# IF_TEST_1.net
KiCad netlist of a schematic drawn in EAGLE
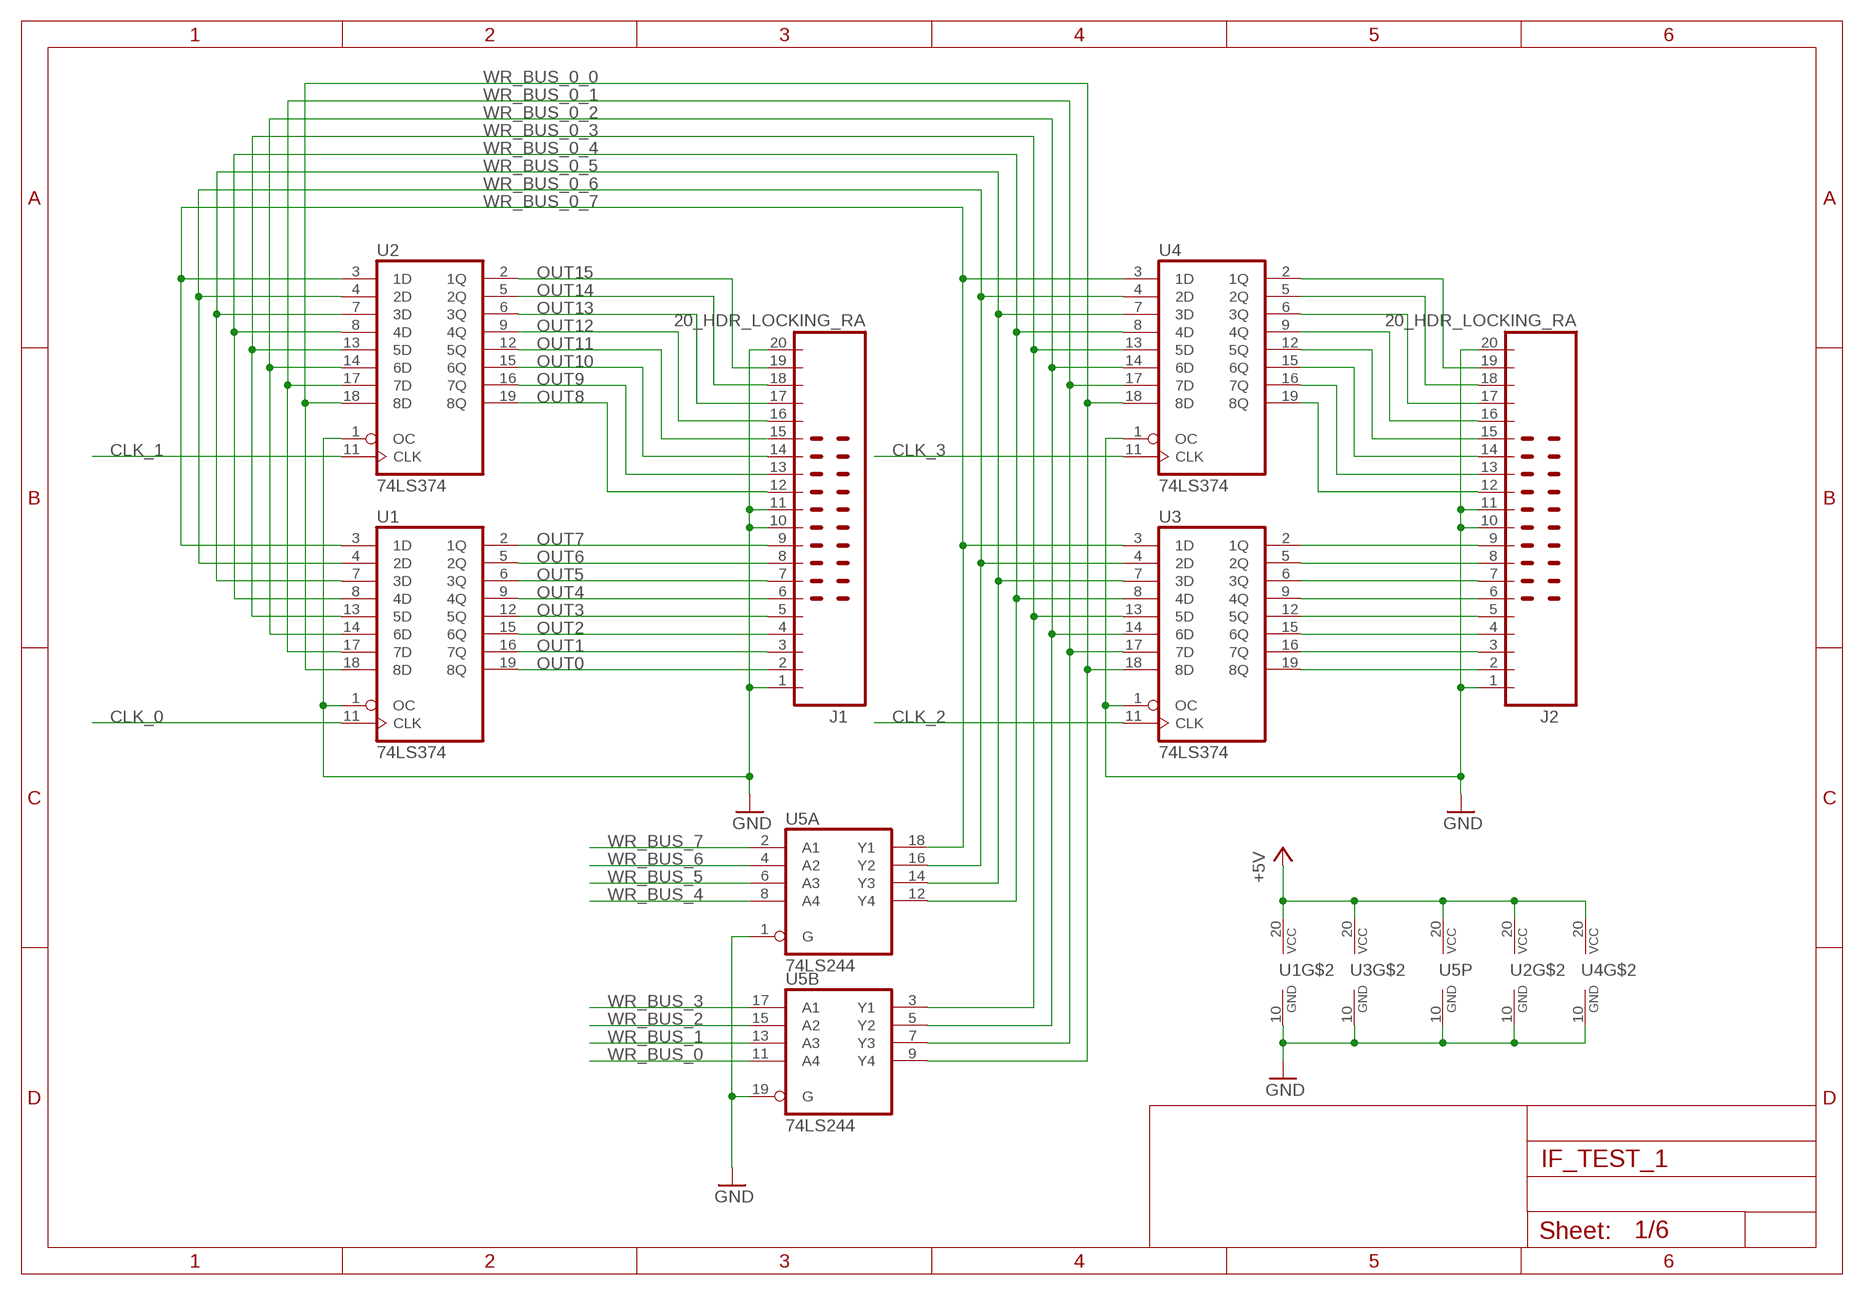
[diagram p0: schematic, sheet 1]
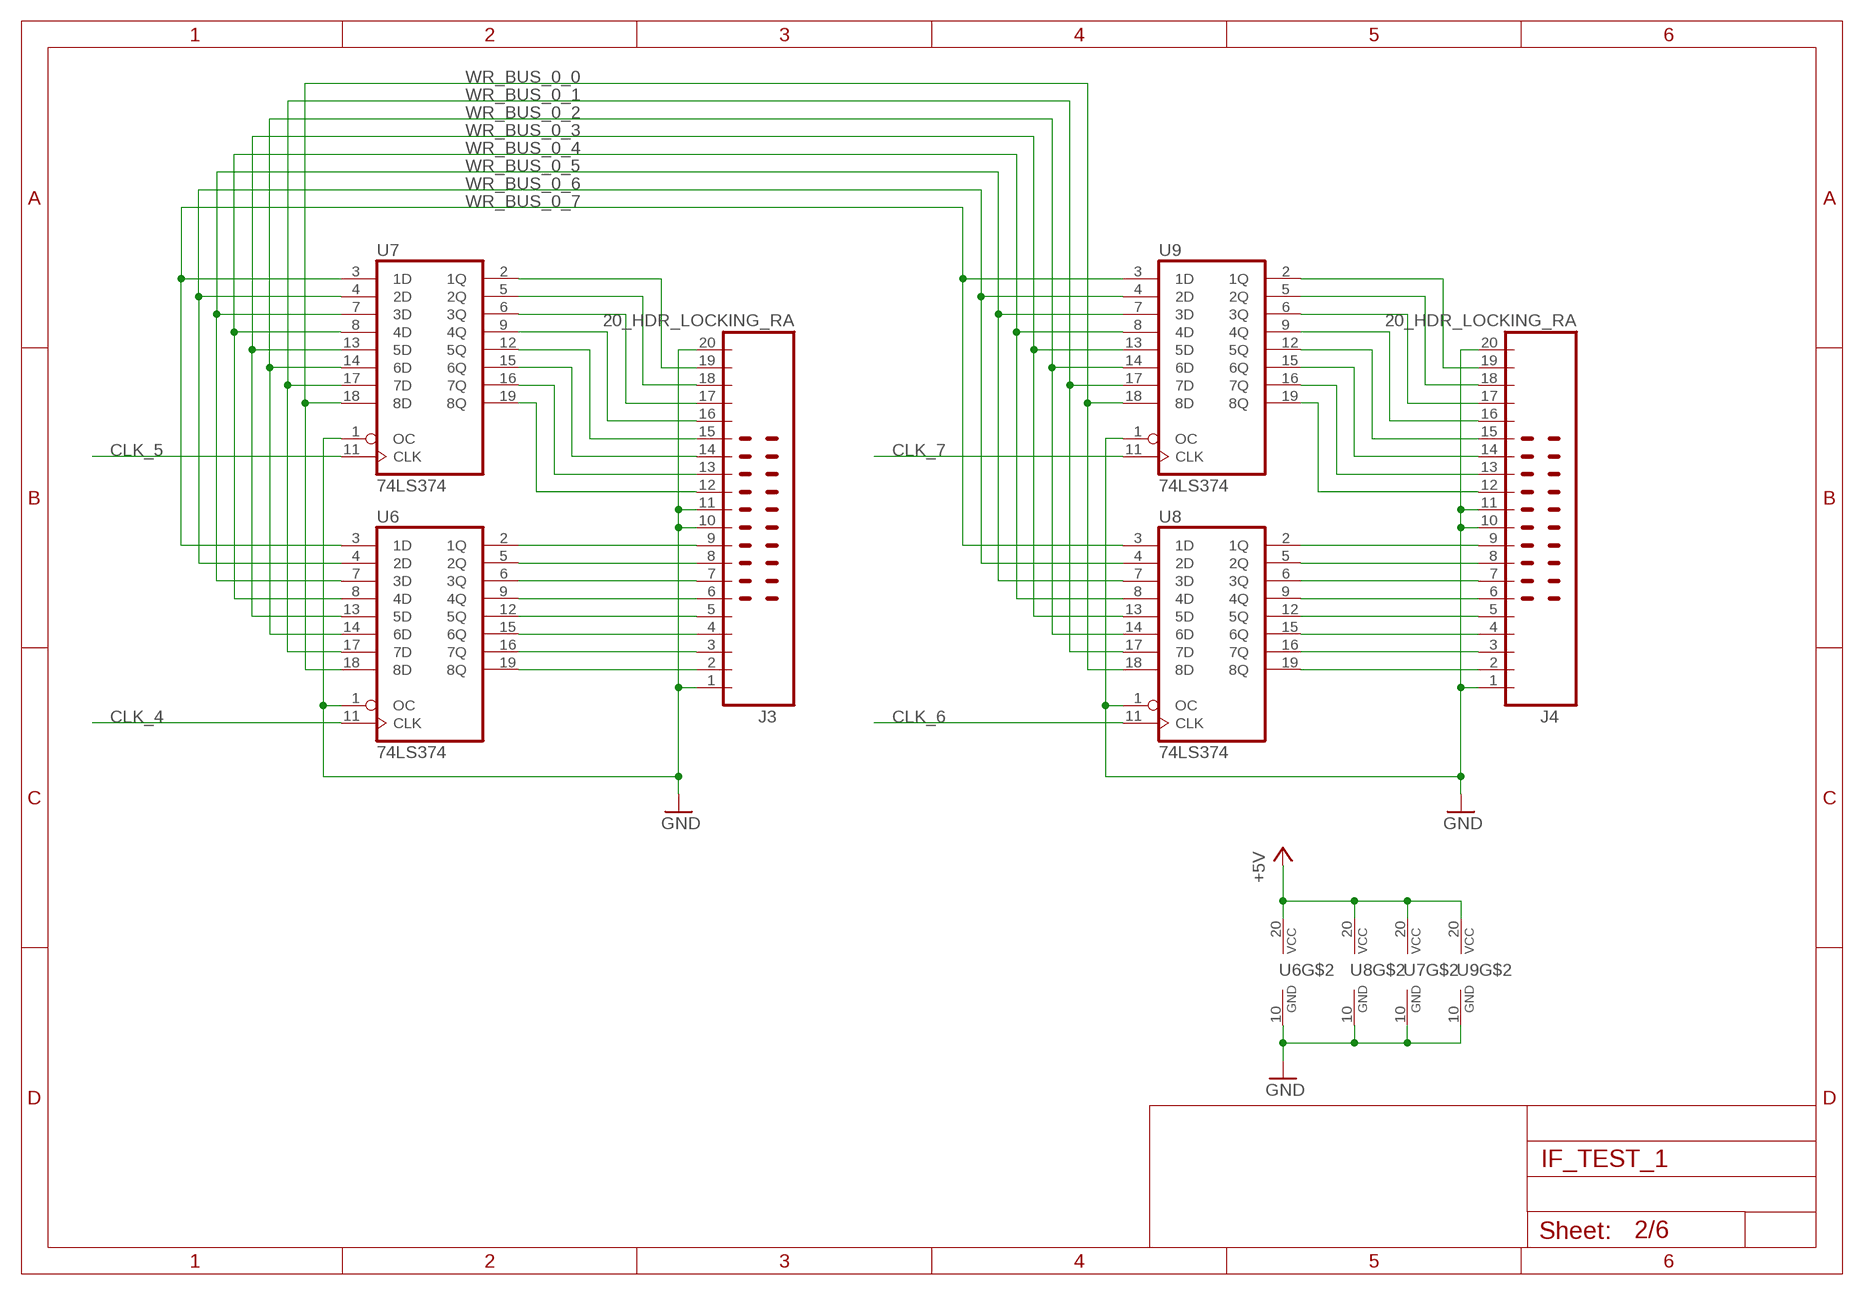
[diagram p1: schematic, sheet 2]
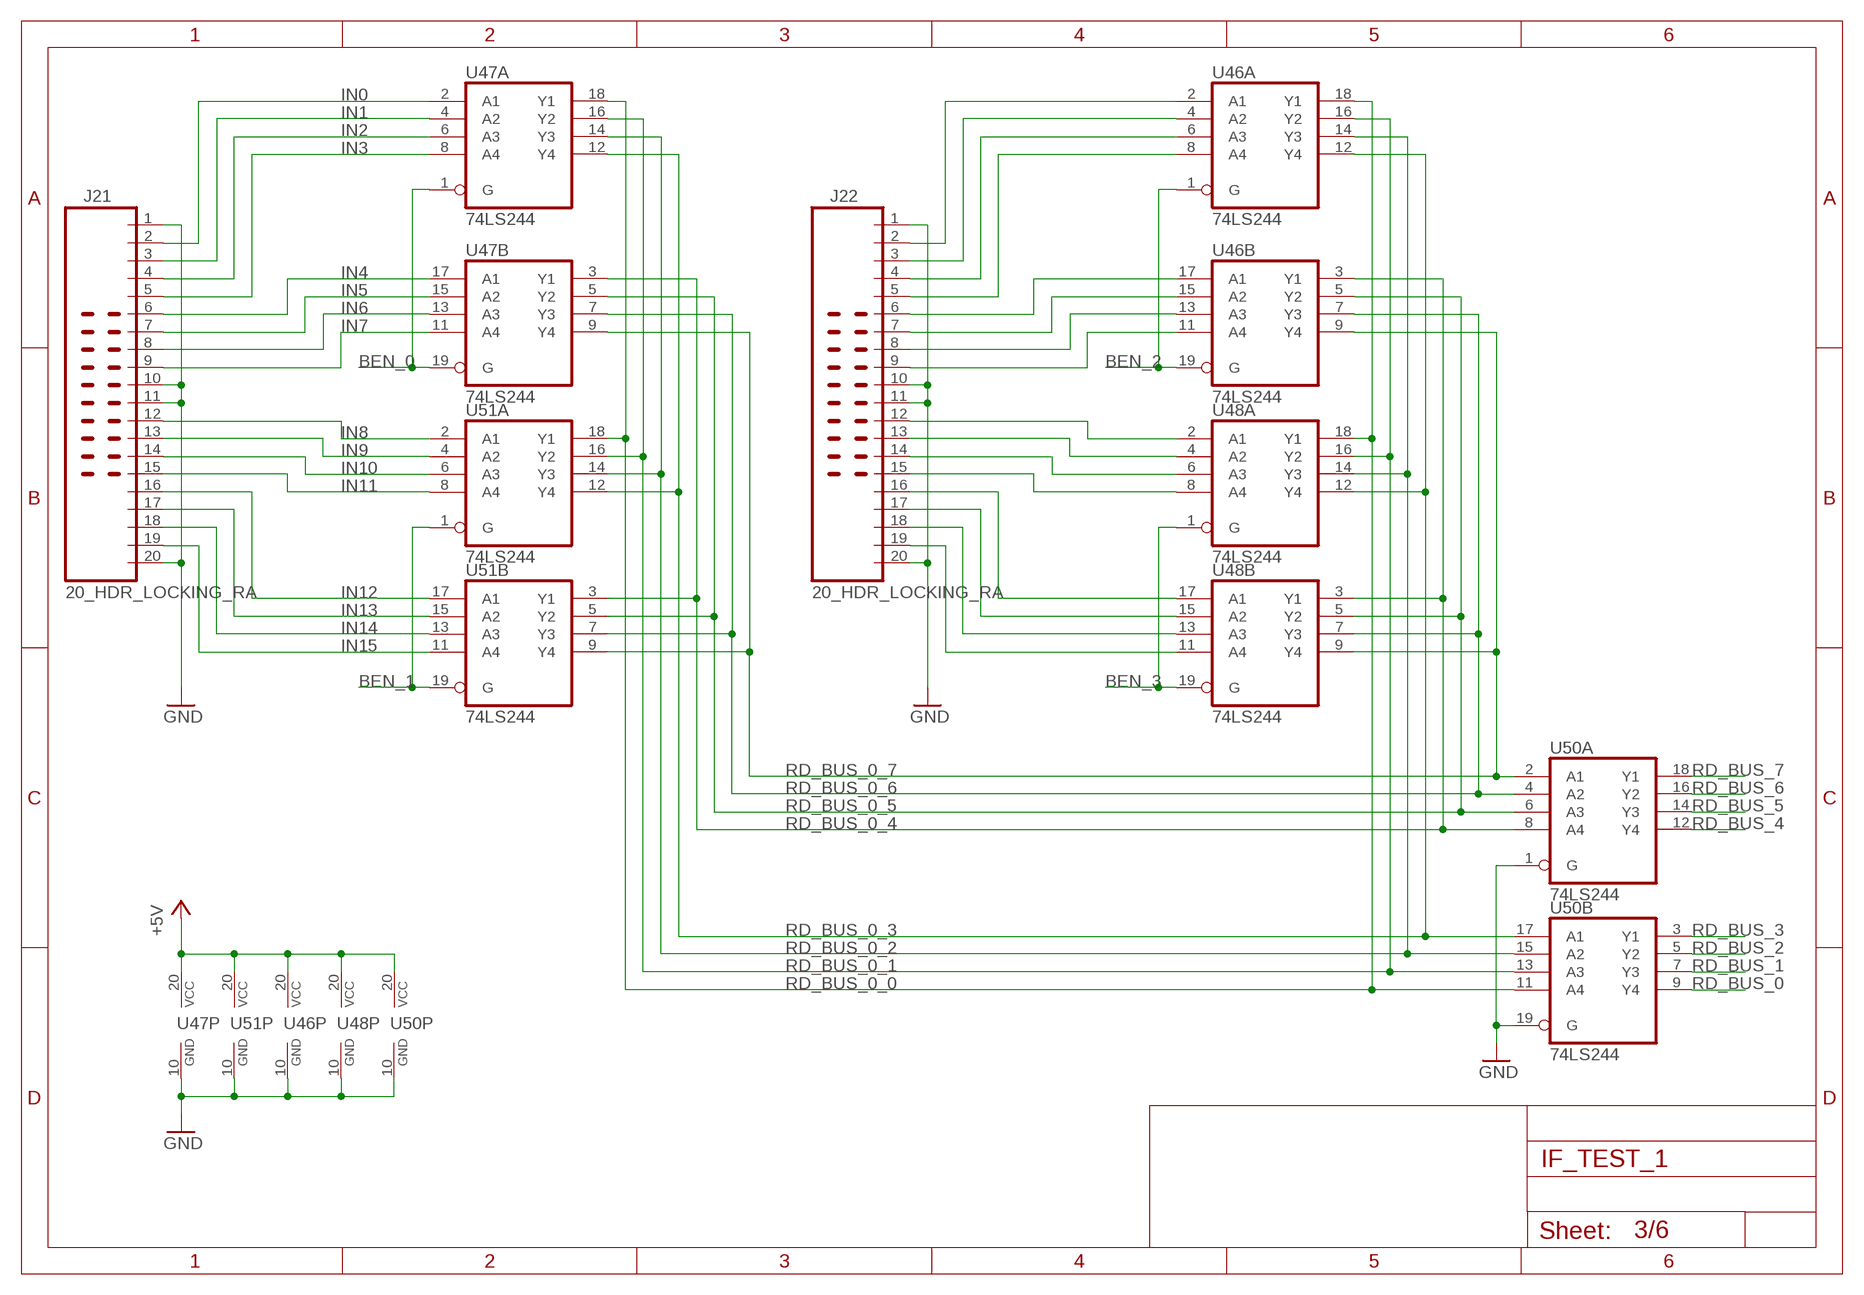
[diagram p2: schematic, sheet 3]
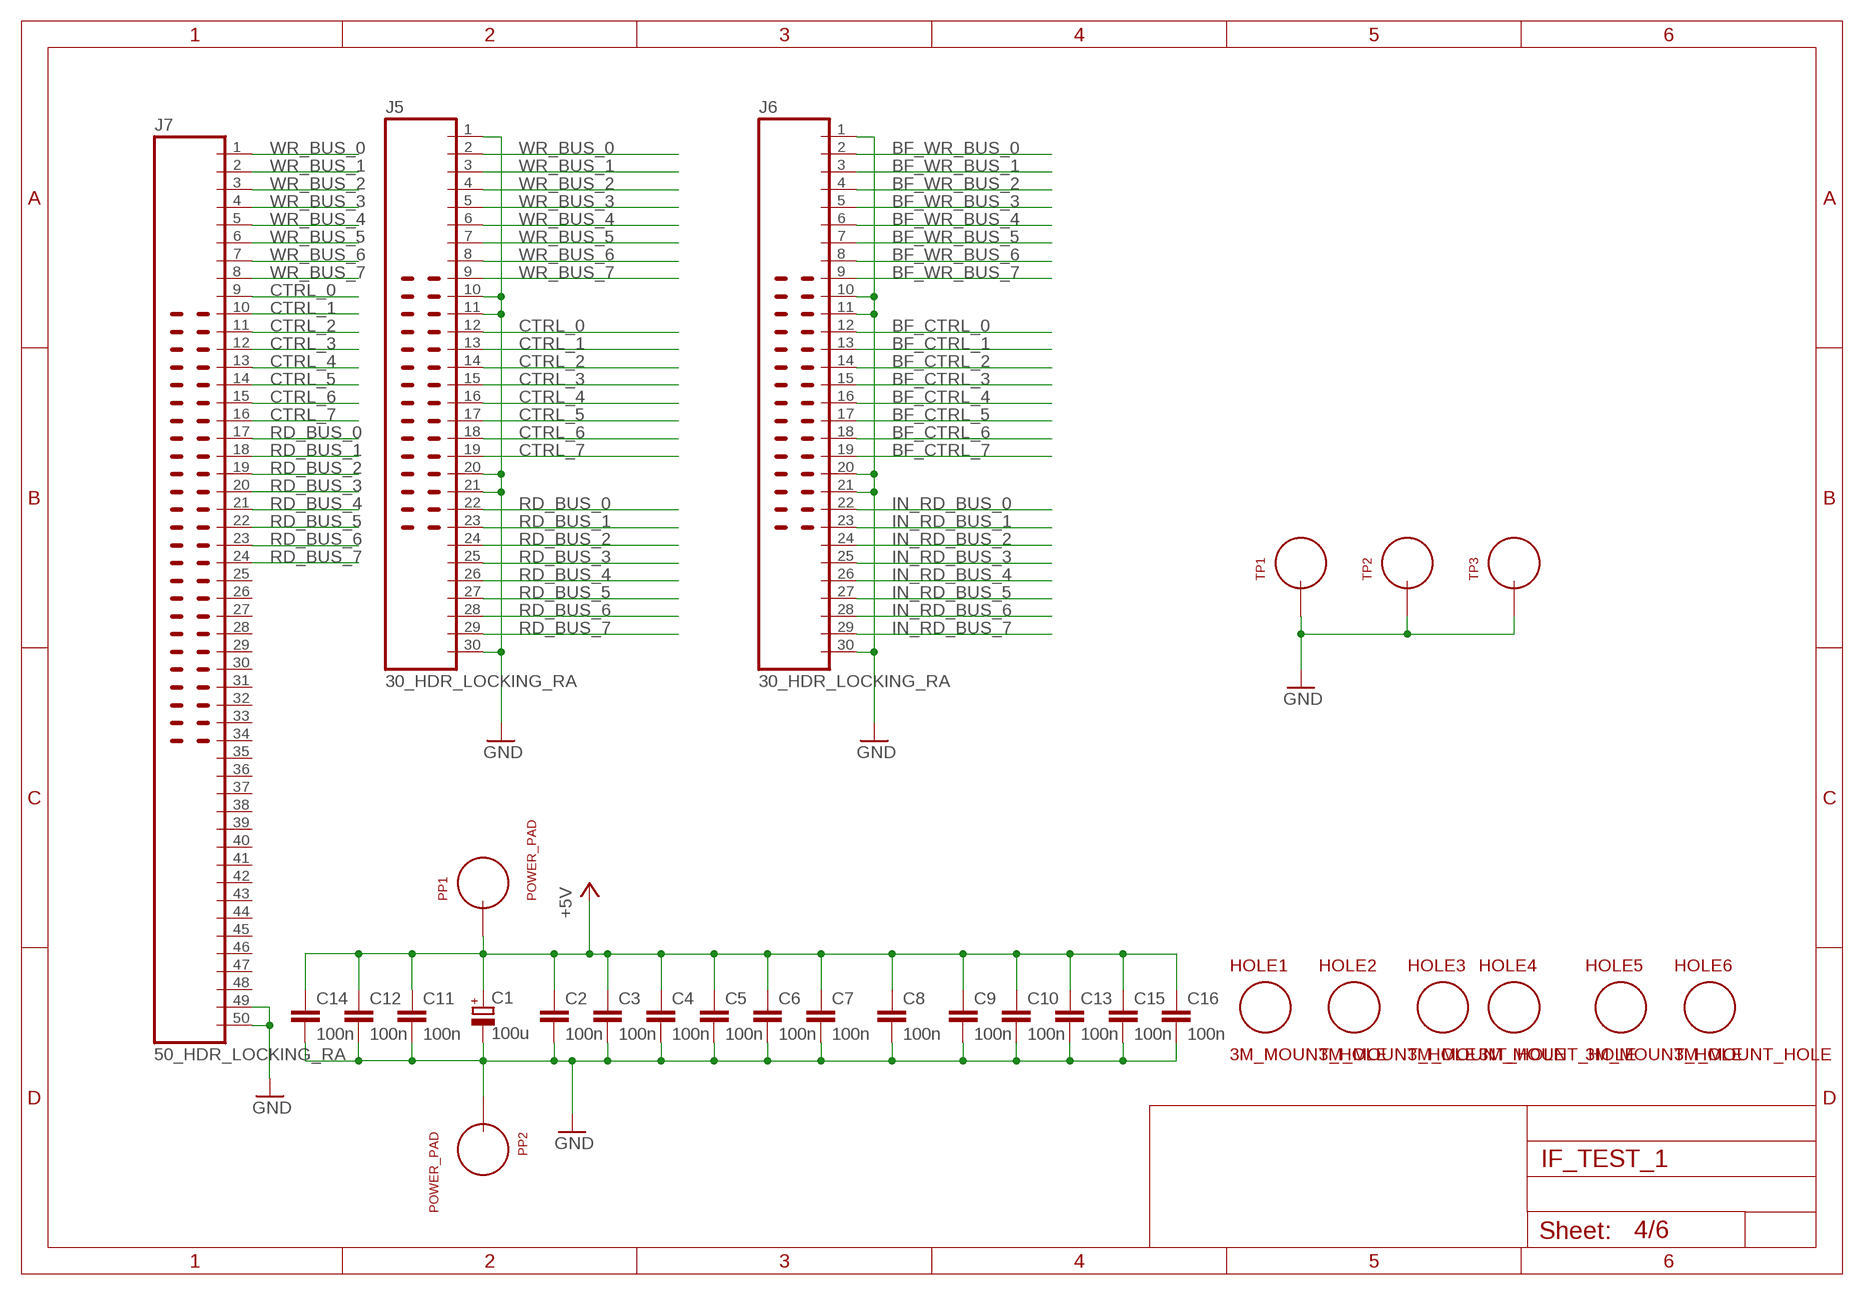
[diagram p3: schematic, sheet 4]
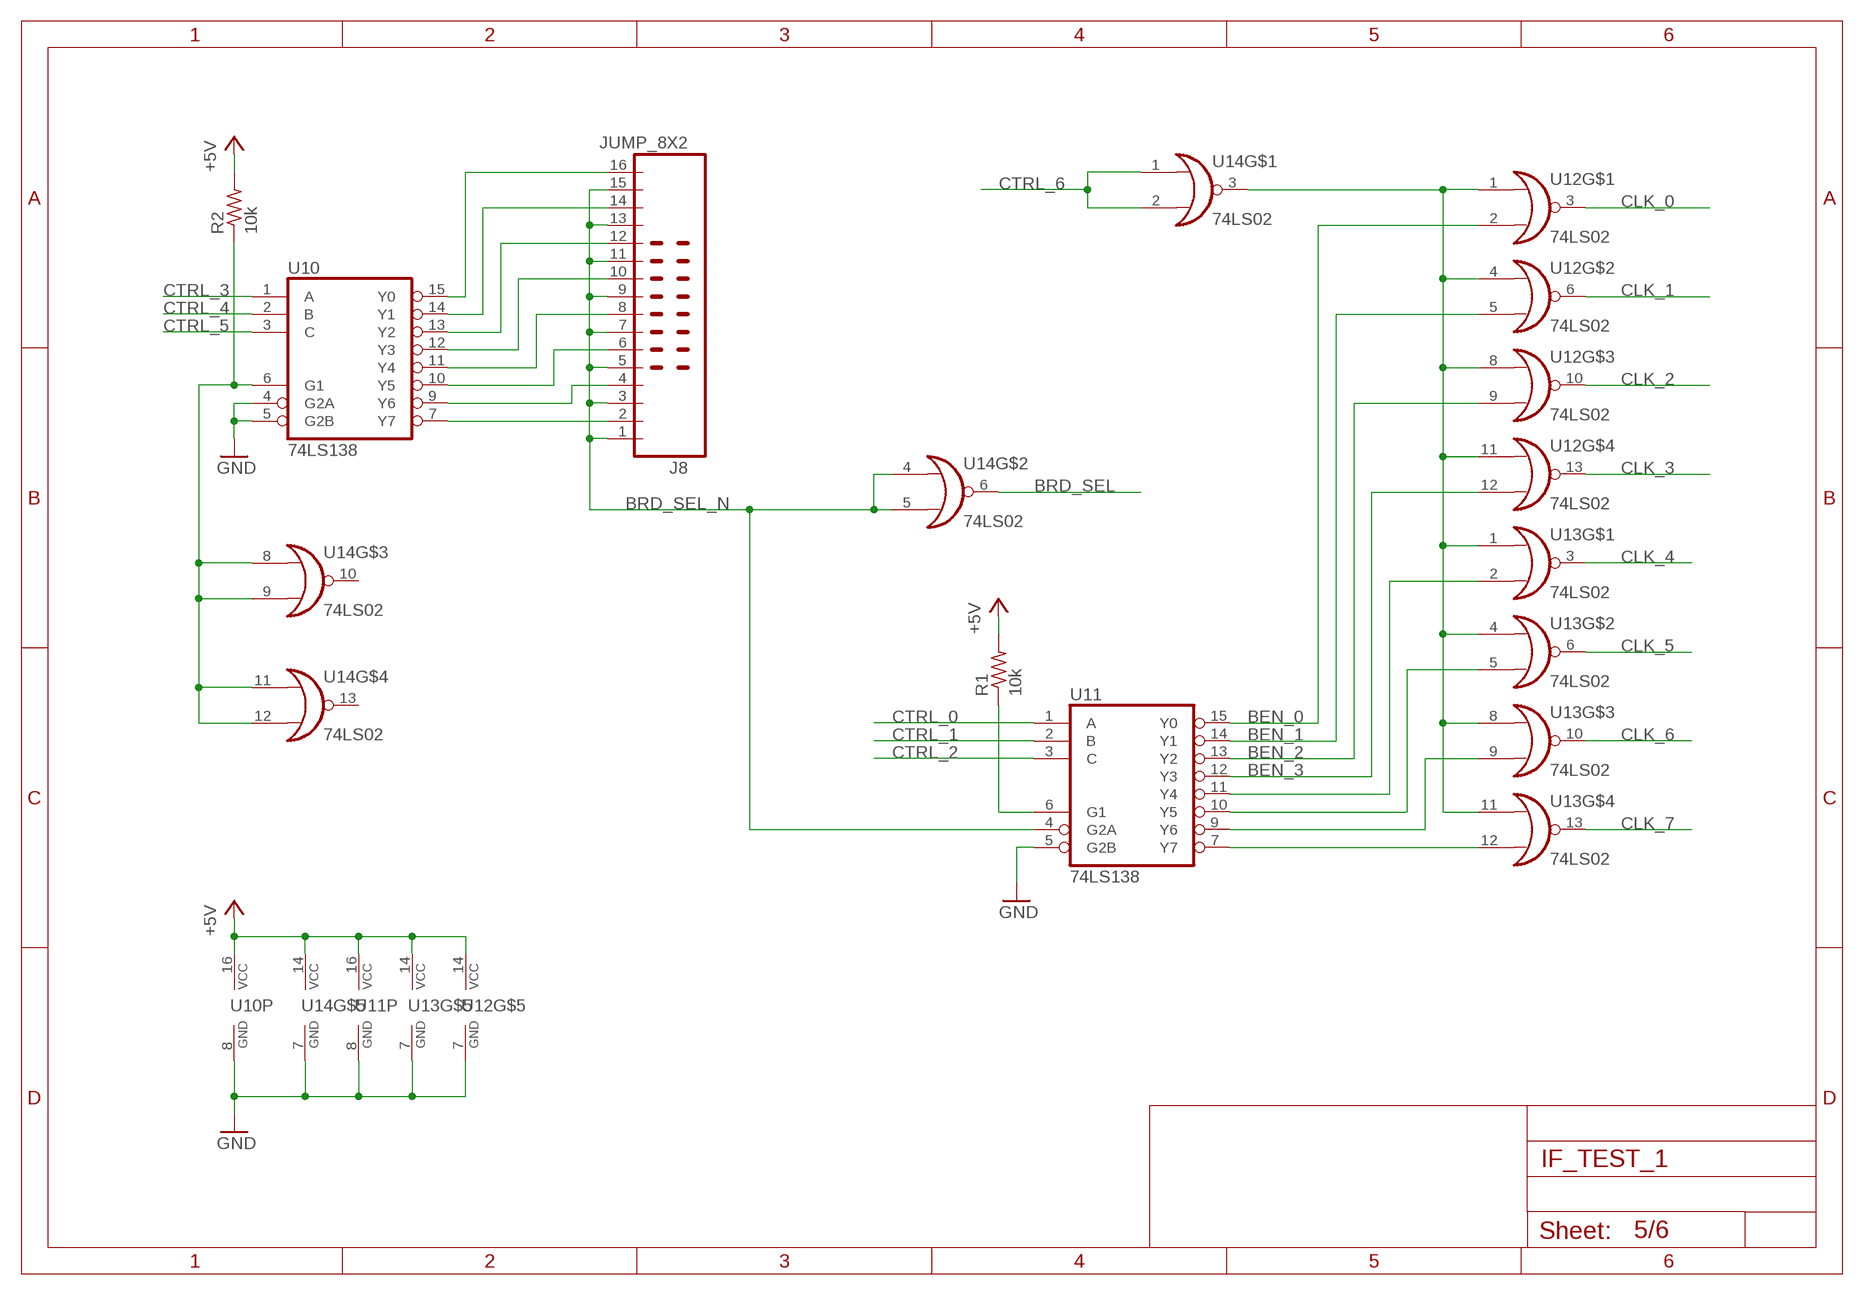
[diagram p4: schematic, sheet 5]
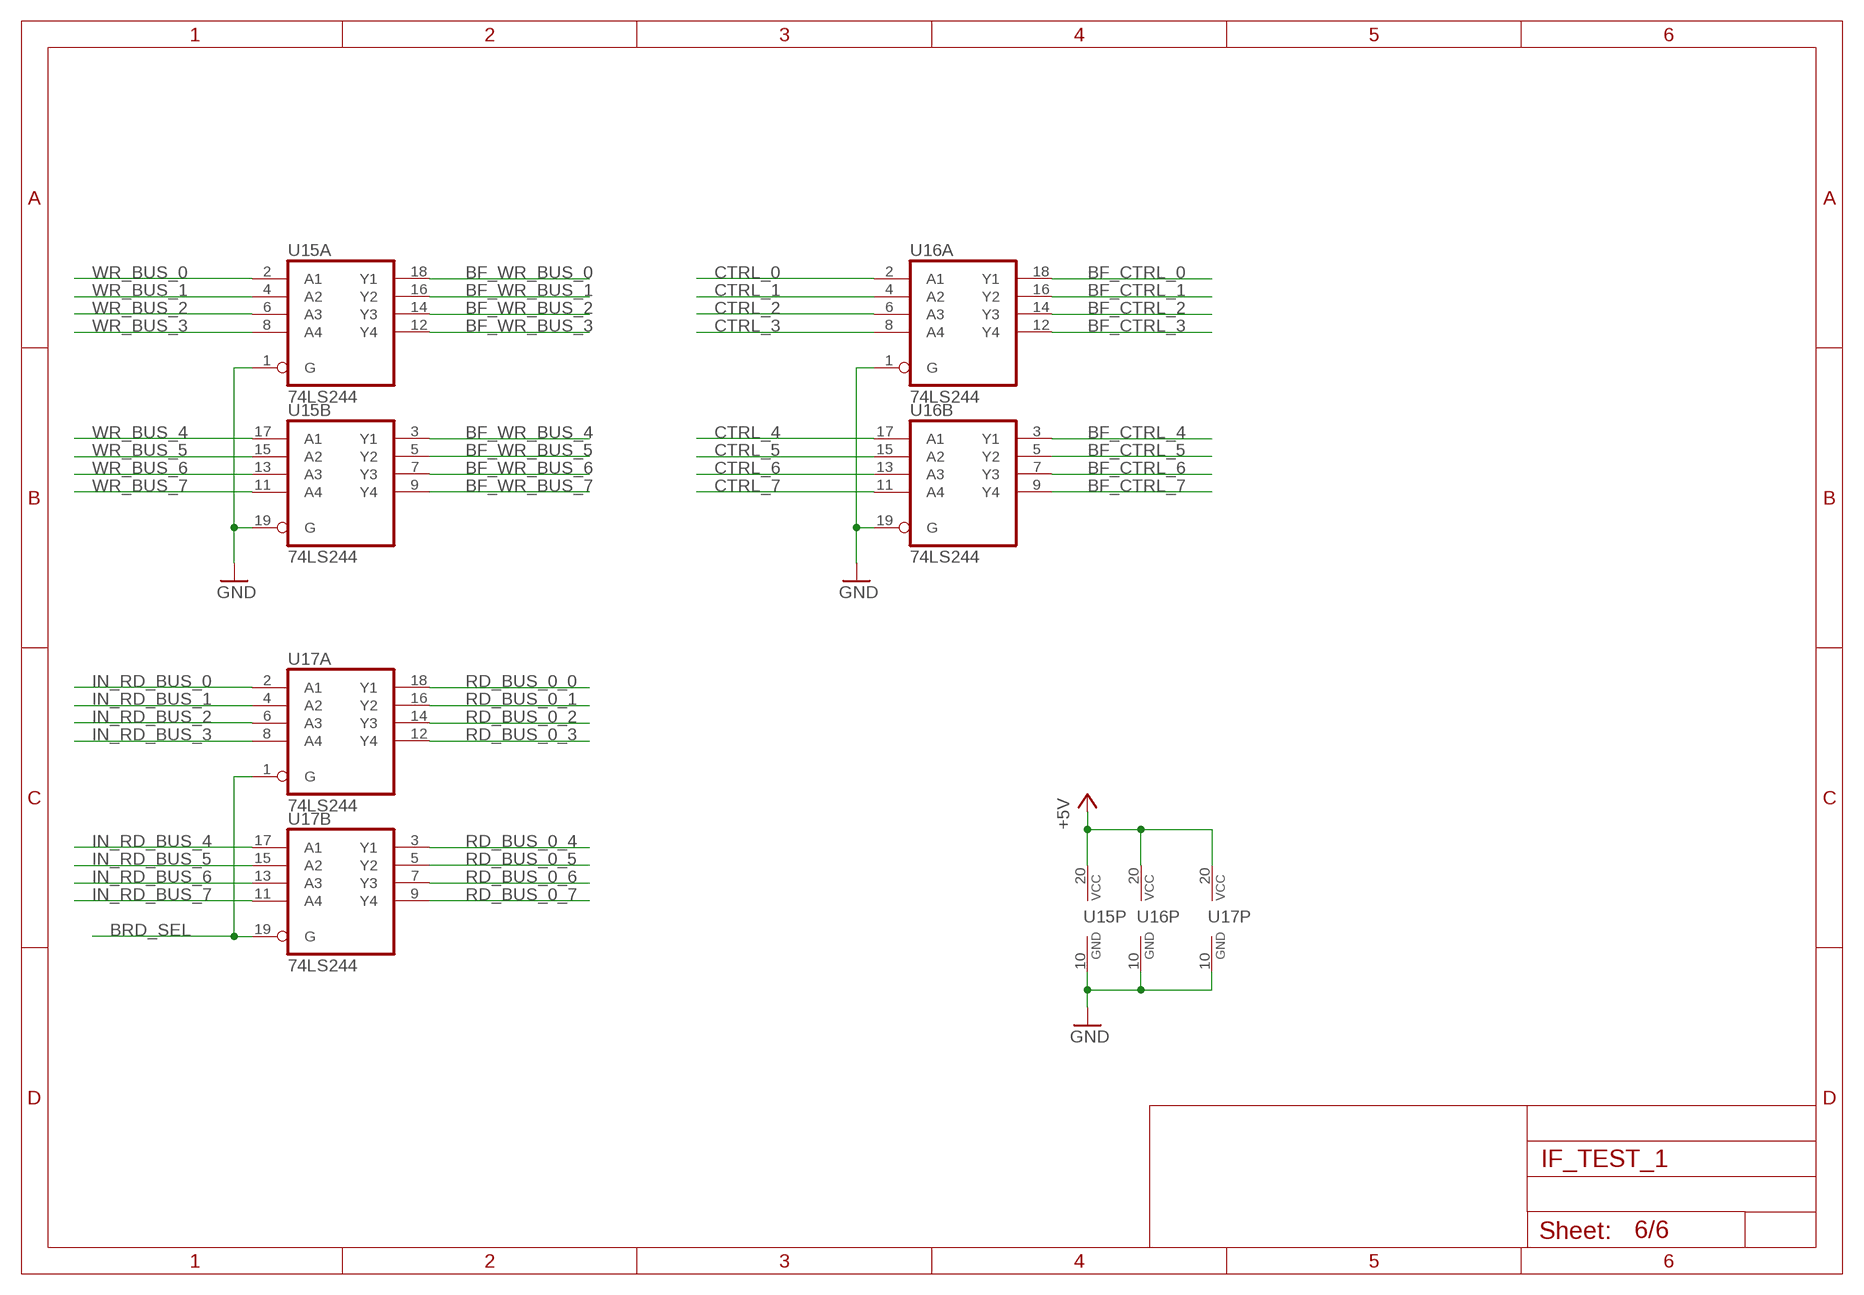
[diagram p5: schematic, sheet 6]

(export (version "E")
  (design (tool "Eeschema 10.0.6"))
  (components
    (comp (ref "J3")
      (value "20_HDR_LOCKING_RA")
      (footprint "eagle-import:20_HDR_LOCKING_RA")
      (libsource (lib "eagle-import") (part "20_HDR_LOCKING_RA"))
    )
    (comp (ref "J4")
      (value "20_HDR_LOCKING_RA")
      (footprint "eagle-import:20_HDR_LOCKING_RA")
      (libsource (lib "eagle-import") (part "20_HDR_LOCKING_RA"))
    )
    (comp (ref "U6")
      (value "74LS374")
      (footprint "eagle-import:DIP20")
      (libsource (lib "eagle-import") (part "74LS374"))
    )
    (comp (ref "U7")
      (value "74LS374")
      (footprint "eagle-import:DIP20")
      (libsource (lib "eagle-import") (part "74LS374"))
    )
    (comp (ref "U8")
      (value "74LS374")
      (footprint "eagle-import:DIP20")
      (libsource (lib "eagle-import") (part "74LS374"))
    )
    (comp (ref "U9")
      (value "74LS374")
      (footprint "eagle-import:DIP20")
      (libsource (lib "eagle-import") (part "74LS374"))
    )
    (comp (ref "J1")
      (value "20_HDR_LOCKING_RA")
      (footprint "eagle-import:20_HDR_LOCKING_RA")
      (libsource (lib "eagle-import") (part "20_HDR_LOCKING_RA"))
    )
    (comp (ref "J2")
      (value "20_HDR_LOCKING_RA")
      (footprint "eagle-import:20_HDR_LOCKING_RA")
      (libsource (lib "eagle-import") (part "20_HDR_LOCKING_RA"))
    )
    (comp (ref "U1")
      (value "74LS374")
      (footprint "eagle-import:DIP20")
      (libsource (lib "eagle-import") (part "74LS374"))
    )
    (comp (ref "U2")
      (value "74LS374")
      (footprint "eagle-import:DIP20")
      (libsource (lib "eagle-import") (part "74LS374"))
    )
    (comp (ref "U3")
      (value "74LS374")
      (footprint "eagle-import:DIP20")
      (libsource (lib "eagle-import") (part "74LS374"))
    )
    (comp (ref "U4")
      (value "74LS374")
      (footprint "eagle-import:DIP20")
      (libsource (lib "eagle-import") (part "74LS374"))
    )
    (comp (ref "U5")
      (value "74LS244")
      (footprint "eagle-import:DIP20")
      (libsource (lib "eagle-import") (part "74LS244"))
    )
    (comp (ref "U15")
      (value "74LS244")
      (footprint "eagle-import:DIP20")
      (libsource (lib "eagle-import") (part "74LS244"))
    )
    (comp (ref "U16")
      (value "74LS244")
      (footprint "eagle-import:DIP20")
      (libsource (lib "eagle-import") (part "74LS244"))
    )
    (comp (ref "U17")
      (value "74LS244")
      (footprint "eagle-import:DIP20")
      (libsource (lib "eagle-import") (part "74LS244"))
    )
    (comp (ref "J21")
      (value "20_HDR_LOCKING_RA")
      (footprint "eagle-import:20_HDR_LOCKING_RA")
      (libsource (lib "eagle-import") (part "20_HDR_LOCKING_RA"))
    )
    (comp (ref "J22")
      (value "20_HDR_LOCKING_RA")
      (footprint "eagle-import:20_HDR_LOCKING_RA")
      (libsource (lib "eagle-import") (part "20_HDR_LOCKING_RA"))
    )
    (comp (ref "U46")
      (value "74LS244")
      (footprint "eagle-import:DIP20")
      (libsource (lib "eagle-import") (part "74LS244"))
    )
    (comp (ref "U47")
      (value "74LS244")
      (footprint "eagle-import:DIP20")
      (libsource (lib "eagle-import") (part "74LS244"))
    )
    (comp (ref "U48")
      (value "74LS244")
      (footprint "eagle-import:DIP20")
      (libsource (lib "eagle-import") (part "74LS244"))
    )
    (comp (ref "U50")
      (value "74LS244")
      (footprint "eagle-import:DIP20")
      (libsource (lib "eagle-import") (part "74LS244"))
    )
    (comp (ref "U51")
      (value "74LS244")
      (footprint "eagle-import:DIP20")
      (libsource (lib "eagle-import") (part "74LS244"))
    )
    (comp (ref "C1")
      (value "100u")
      (footprint "eagle-import:POLARISED_CAP_2P5_6P3MM")
      (libsource (lib "eagle-import") (part "POLARISED_CAP_2P5_6P3MM"))
    )
    (comp (ref "C2")
      (value "100n")
      (footprint "eagle-import:CAP_P2INCH")
      (libsource (lib "eagle-import") (part "C_P2INCH"))
    )
    (comp (ref "C3")
      (value "100n")
      (footprint "eagle-import:CAP_P2INCH")
      (libsource (lib "eagle-import") (part "C_P2INCH"))
    )
    (comp (ref "C4")
      (value "100n")
      (footprint "eagle-import:CAP_P2INCH")
      (libsource (lib "eagle-import") (part "C_P2INCH"))
    )
    (comp (ref "C5")
      (value "100n")
      (footprint "eagle-import:CAP_P2INCH")
      (libsource (lib "eagle-import") (part "C_P2INCH"))
    )
    (comp (ref "C6")
      (value "100n")
      (footprint "eagle-import:CAP_P2INCH")
      (libsource (lib "eagle-import") (part "C_P2INCH"))
    )
    (comp (ref "C7")
      (value "100n")
      (footprint "eagle-import:CAP_P2INCH")
      (libsource (lib "eagle-import") (part "C_P2INCH"))
    )
    (comp (ref "C8")
      (value "100n")
      (footprint "eagle-import:CAP_P2INCH")
      (libsource (lib "eagle-import") (part "C_P2INCH"))
    )
    (comp (ref "C9")
      (value "100n")
      (footprint "eagle-import:CAP_P2INCH")
      (libsource (lib "eagle-import") (part "C_P2INCH"))
    )
    (comp (ref "C10")
      (value "100n")
      (footprint "eagle-import:CAP_P2INCH")
      (libsource (lib "eagle-import") (part "C_P2INCH"))
    )
    (comp (ref "C11")
      (value "100n")
      (footprint "eagle-import:CAP_P2INCH")
      (libsource (lib "eagle-import") (part "C_P2INCH"))
    )
    (comp (ref "C12")
      (value "100n")
      (footprint "eagle-import:CAP_P2INCH")
      (libsource (lib "eagle-import") (part "C_P2INCH"))
    )
    (comp (ref "C13")
      (value "100n")
      (footprint "eagle-import:CAP_P2INCH")
      (libsource (lib "eagle-import") (part "C_P2INCH"))
    )
    (comp (ref "C14")
      (value "100n")
      (footprint "eagle-import:CAP_P2INCH")
      (libsource (lib "eagle-import") (part "C_P2INCH"))
    )
    (comp (ref "C15")
      (value "100n")
      (footprint "eagle-import:CAP_P2INCH")
      (libsource (lib "eagle-import") (part "C_P2INCH"))
    )
    (comp (ref "C16")
      (value "100n")
      (footprint "eagle-import:CAP_P2INCH")
      (libsource (lib "eagle-import") (part "C_P2INCH"))
    )
    (comp (ref "HOLE1")
      (value "3M_MOUNT_HOLE")
      (footprint "eagle-import:3M_HOLE")
      (libsource (lib "eagle-import") (part "3M_MOUNT_HOLE"))
    )
    (comp (ref "HOLE2")
      (value "3M_MOUNT_HOLE")
      (footprint "eagle-import:3M_HOLE")
      (libsource (lib "eagle-import") (part "3M_MOUNT_HOLE"))
    )
    (comp (ref "HOLE3")
      (value "3M_MOUNT_HOLE")
      (footprint "eagle-import:3M_HOLE")
      (libsource (lib "eagle-import") (part "3M_MOUNT_HOLE"))
    )
    (comp (ref "HOLE4")
      (value "3M_MOUNT_HOLE")
      (footprint "eagle-import:3M_HOLE")
      (libsource (lib "eagle-import") (part "3M_MOUNT_HOLE"))
    )
    (comp (ref "HOLE5")
      (value "3M_MOUNT_HOLE")
      (footprint "eagle-import:3M_HOLE")
      (libsource (lib "eagle-import") (part "3M_MOUNT_HOLE"))
    )
    (comp (ref "HOLE6")
      (value "3M_MOUNT_HOLE")
      (footprint "eagle-import:3M_HOLE")
      (libsource (lib "eagle-import") (part "3M_MOUNT_HOLE"))
    )
    (comp (ref "J5")
      (value "30_HDR_LOCKING_RA")
      (footprint "eagle-import:30_HDR_LOCKING_RA")
      (libsource (lib "eagle-import") (part "30_HDR_LOCKING_RA"))
    )
    (comp (ref "J6")
      (value "30_HDR_LOCKING_RA")
      (footprint "eagle-import:30_HDR_LOCKING_RA")
      (libsource (lib "eagle-import") (part "30_HDR_LOCKING_RA"))
    )
    (comp (ref "J7")
      (value "50_HDR_LOCKING_RA")
      (footprint "eagle-import:50_HDR_LOCKING_RA")
      (libsource (lib "eagle-import") (part "50_HDR_LOCKING_RA"))
    )
    (comp (ref "PP1")
      (value "POWER_PAD")
      (footprint "eagle-import:POWER_PAD")
      (libsource (lib "eagle-import") (part "POWER_PAD"))
    )
    (comp (ref "PP2")
      (value "POWER_PAD")
      (footprint "eagle-import:POWER_PAD")
      (libsource (lib "eagle-import") (part "POWER_PAD"))
    )
    (comp (ref "TP1")
      (value "TEST_LOOP")
      (footprint "eagle-import:TEST_LOOP")
      (libsource (lib "eagle-import") (part "TEST_LOOP"))
    )
    (comp (ref "TP2")
      (value "TEST_LOOP")
      (footprint "eagle-import:TEST_LOOP")
      (libsource (lib "eagle-import") (part "TEST_LOOP"))
    )
    (comp (ref "TP3")
      (value "TEST_LOOP")
      (footprint "eagle-import:TEST_LOOP")
      (libsource (lib "eagle-import") (part "TEST_LOOP"))
    )
    (comp (ref "J8")
      (value "JUMP_8X2")
      (footprint "eagle-import:JUMP_8X2")
      (libsource (lib "eagle-import") (part "JUMP_8X2"))
    )
    (comp (ref "R1")
      (value "10k")
      (footprint "eagle-import:R_P2INCH")
      (libsource (lib "eagle-import") (part "R_P2INCH"))
    )
    (comp (ref "R2")
      (value "10k")
      (footprint "eagle-import:R_P2INCH")
      (libsource (lib "eagle-import") (part "R_P2INCH"))
    )
    (comp (ref "U10")
      (value "74LS138")
      (footprint "eagle-import:DIP16")
      (libsource (lib "eagle-import") (part "74LS138"))
    )
    (comp (ref "U11")
      (value "74LS138")
      (footprint "eagle-import:DIP16")
      (libsource (lib "eagle-import") (part "74LS138"))
    )
    (comp (ref "U12")
      (value "74LS02")
      (footprint "eagle-import:DIP14")
      (libsource (lib "eagle-import") (part "74LS02"))
    )
    (comp (ref "U13")
      (value "74LS02")
      (footprint "eagle-import:DIP14")
      (libsource (lib "eagle-import") (part "74LS02"))
    )
    (comp (ref "U14")
      (value "74LS02")
      (footprint "eagle-import:DIP14")
      (libsource (lib "eagle-import") (part "74LS02"))
    )
  )
  (nets
    (net (code "1") (name "+5V") (class "Default")
      (node (ref "C1") (pin "A") (pinfunction "A_A") (pintype "passive"))
      (node (ref "C10") (pin "1") (pinfunction "1_1") (pintype "passive"))
      (node (ref "C11") (pin "1") (pinfunction "1_1") (pintype "passive"))
      (node (ref "C12") (pin "1") (pinfunction "1_1") (pintype "passive"))
      (node (ref "C13") (pin "1") (pinfunction "1_1") (pintype "passive"))
      (node (ref "C14") (pin "1") (pinfunction "1_1") (pintype "passive"))
      (node (ref "C15") (pin "1") (pinfunction "1_1") (pintype "passive"))
      (node (ref "C16") (pin "1") (pinfunction "1_1") (pintype "passive"))
      (node (ref "C2") (pin "1") (pinfunction "1_1") (pintype "passive"))
      (node (ref "C3") (pin "1") (pinfunction "1_1") (pintype "passive"))
      (node (ref "C4") (pin "1") (pinfunction "1_1") (pintype "passive"))
      (node (ref "C5") (pin "1") (pinfunction "1_1") (pintype "passive"))
      (node (ref "C6") (pin "1") (pinfunction "1_1") (pintype "passive"))
      (node (ref "C7") (pin "1") (pinfunction "1_1") (pintype "passive"))
      (node (ref "C8") (pin "1") (pinfunction "1_1") (pintype "passive"))
      (node (ref "C9") (pin "1") (pinfunction "1_1") (pintype "passive"))
      (node (ref "PP1") (pin "1") (pinfunction "P$1_1") (pintype "bidirectional"))
      (node (ref "R1") (pin "2") (pinfunction "2_2") (pintype "passive"))
      (node (ref "R2") (pin "2") (pinfunction "2_2") (pintype "passive"))
      (node (ref "U1") (pin "20") (pinfunction "VCC_20") (pintype "power_in"))
      (node (ref "U10") (pin "16") (pinfunction "VCC_16") (pintype "power_in"))
      (node (ref "U11") (pin "16") (pinfunction "VCC_16") (pintype "power_in"))
      (node (ref "U12") (pin "14") (pinfunction "VCC_14") (pintype "power_in"))
      (node (ref "U13") (pin "14") (pinfunction "VCC_14") (pintype "power_in"))
      (node (ref "U14") (pin "14") (pinfunction "VCC_14") (pintype "power_in"))
      (node (ref "U15") (pin "20") (pinfunction "VCC_20") (pintype "power_in"))
      (node (ref "U16") (pin "20") (pinfunction "VCC_20") (pintype "power_in"))
      (node (ref "U17") (pin "20") (pinfunction "VCC_20") (pintype "power_in"))
      (node (ref "U2") (pin "20") (pinfunction "VCC_20") (pintype "power_in"))
      (node (ref "U3") (pin "20") (pinfunction "VCC_20") (pintype "power_in"))
      (node (ref "U4") (pin "20") (pinfunction "VCC_20") (pintype "power_in"))
      (node (ref "U46") (pin "20") (pinfunction "VCC_20") (pintype "power_in"))
      (node (ref "U47") (pin "20") (pinfunction "VCC_20") (pintype "power_in"))
      (node (ref "U48") (pin "20") (pinfunction "VCC_20") (pintype "power_in"))
      (node (ref "U5") (pin "20") (pinfunction "VCC_20") (pintype "power_in"))
      (node (ref "U50") (pin "20") (pinfunction "VCC_20") (pintype "power_in"))
      (node (ref "U51") (pin "20") (pinfunction "VCC_20") (pintype "power_in"))
      (node (ref "U6") (pin "20") (pinfunction "VCC_20") (pintype "power_in"))
      (node (ref "U7") (pin "20") (pinfunction "VCC_20") (pintype "power_in"))
      (node (ref "U8") (pin "20") (pinfunction "VCC_20") (pintype "power_in"))
      (node (ref "U9") (pin "20") (pinfunction "VCC_20") (pintype "power_in"))
    )
    (net (code "2") (name "BEN_0") (class "Default")
      (node (ref "U11") (pin "15") (pinfunction "Y0_15") (pintype "output"))
      (node (ref "U12") (pin "2") (pinfunction "I1_2") (pintype "input"))
      (node (ref "U47") (pin "1") (pinfunction "G_1") (pintype "input"))
      (node (ref "U47") (pin "19") (pinfunction "G_19") (pintype "input"))
    )
    (net (code "3") (name "BEN_1") (class "Default")
      (node (ref "U11") (pin "14") (pinfunction "Y1_14") (pintype "output"))
      (node (ref "U12") (pin "5") (pinfunction "I1_5") (pintype "input"))
      (node (ref "U51") (pin "1") (pinfunction "G_1") (pintype "input"))
      (node (ref "U51") (pin "19") (pinfunction "G_19") (pintype "input"))
    )
    (net (code "4") (name "BEN_2") (class "Default")
      (node (ref "U11") (pin "13") (pinfunction "Y2_13") (pintype "output"))
      (node (ref "U12") (pin "9") (pinfunction "I1_9") (pintype "input"))
      (node (ref "U46") (pin "1") (pinfunction "G_1") (pintype "input"))
      (node (ref "U46") (pin "19") (pinfunction "G_19") (pintype "input"))
    )
    (net (code "5") (name "BEN_3") (class "Default")
      (node (ref "U11") (pin "12") (pinfunction "Y3_12") (pintype "output"))
      (node (ref "U12") (pin "12") (pinfunction "I1_12") (pintype "input"))
      (node (ref "U48") (pin "1") (pinfunction "G_1") (pintype "input"))
      (node (ref "U48") (pin "19") (pinfunction "G_19") (pintype "input"))
    )
    (net (code "6") (name "BF_CTRL_0") (class "Default")
      (node (ref "J6") (pin "12") (pinfunction "12_12") (pintype "bidirectional"))
      (node (ref "U16") (pin "18") (pinfunction "Y1_18") (pintype "tri_state"))
    )
    (net (code "7") (name "BF_CTRL_1") (class "Default")
      (node (ref "J6") (pin "13") (pinfunction "13_13") (pintype "bidirectional"))
      (node (ref "U16") (pin "16") (pinfunction "Y2_16") (pintype "tri_state"))
    )
    (net (code "8") (name "BF_CTRL_2") (class "Default")
      (node (ref "J6") (pin "14") (pinfunction "14_14") (pintype "bidirectional"))
      (node (ref "U16") (pin "14") (pinfunction "Y3_14") (pintype "tri_state"))
    )
    (net (code "9") (name "BF_CTRL_3") (class "Default")
      (node (ref "J6") (pin "15") (pinfunction "15_15") (pintype "bidirectional"))
      (node (ref "U16") (pin "12") (pinfunction "Y4_12") (pintype "tri_state"))
    )
    (net (code "10") (name "BF_CTRL_4") (class "Default")
      (node (ref "J6") (pin "16") (pinfunction "16_16") (pintype "bidirectional"))
      (node (ref "U16") (pin "3") (pinfunction "Y1_3") (pintype "tri_state"))
    )
    (net (code "11") (name "BF_CTRL_5") (class "Default")
      (node (ref "J6") (pin "17") (pinfunction "17_17") (pintype "bidirectional"))
      (node (ref "U16") (pin "5") (pinfunction "Y2_5") (pintype "tri_state"))
    )
    (net (code "12") (name "BF_CTRL_6") (class "Default")
      (node (ref "J6") (pin "18") (pinfunction "18_18") (pintype "bidirectional"))
      (node (ref "U16") (pin "7") (pinfunction "Y3_7") (pintype "tri_state"))
    )
    (net (code "13") (name "BF_CTRL_7") (class "Default")
      (node (ref "J6") (pin "19") (pinfunction "19_19") (pintype "bidirectional"))
      (node (ref "U16") (pin "9") (pinfunction "Y4_9") (pintype "tri_state"))
    )
    (net (code "14") (name "BF_WR_BUS_0") (class "Default")
      (node (ref "J6") (pin "2") (pinfunction "2_2") (pintype "bidirectional"))
      (node (ref "U15") (pin "18") (pinfunction "Y1_18") (pintype "tri_state"))
    )
    (net (code "15") (name "BF_WR_BUS_1") (class "Default")
      (node (ref "J6") (pin "3") (pinfunction "3_3") (pintype "bidirectional"))
      (node (ref "U15") (pin "16") (pinfunction "Y2_16") (pintype "tri_state"))
    )
    (net (code "16") (name "BF_WR_BUS_2") (class "Default")
      (node (ref "J6") (pin "4") (pinfunction "4_4") (pintype "bidirectional"))
      (node (ref "U15") (pin "14") (pinfunction "Y3_14") (pintype "tri_state"))
    )
    (net (code "17") (name "BF_WR_BUS_3") (class "Default")
      (node (ref "J6") (pin "5") (pinfunction "5_5") (pintype "bidirectional"))
      (node (ref "U15") (pin "12") (pinfunction "Y4_12") (pintype "tri_state"))
    )
    (net (code "18") (name "BF_WR_BUS_4") (class "Default")
      (node (ref "J6") (pin "6") (pinfunction "6_6") (pintype "bidirectional"))
      (node (ref "U15") (pin "3") (pinfunction "Y1_3") (pintype "tri_state"))
    )
    (net (code "19") (name "BF_WR_BUS_5") (class "Default")
      (node (ref "J6") (pin "7") (pinfunction "7_7") (pintype "bidirectional"))
      (node (ref "U15") (pin "5") (pinfunction "Y2_5") (pintype "tri_state"))
    )
    (net (code "20") (name "BF_WR_BUS_6") (class "Default")
      (node (ref "J6") (pin "8") (pinfunction "8_8") (pintype "bidirectional"))
      (node (ref "U15") (pin "7") (pinfunction "Y3_7") (pintype "tri_state"))
    )
    (net (code "21") (name "BF_WR_BUS_7") (class "Default")
      (node (ref "J6") (pin "9") (pinfunction "9_9") (pintype "bidirectional"))
      (node (ref "U15") (pin "9") (pinfunction "Y4_9") (pintype "tri_state"))
    )
    (net (code "22") (name "BRD_SEL") (class "Default")
      (node (ref "U14") (pin "6") (pinfunction "O_6") (pintype "output"))
      (node (ref "U17") (pin "1") (pinfunction "G_1") (pintype "input"))
      (node (ref "U17") (pin "19") (pinfunction "G_19") (pintype "input"))
    )
    (net (code "23") (name "BRD_SEL_N") (class "Default")
      (node (ref "J8") (pin "1") (pinfunction "1_1") (pintype "bidirectional"))
      (node (ref "J8") (pin "11") (pinfunction "11_11") (pintype "bidirectional"))
      (node (ref "J8") (pin "13") (pinfunction "13_13") (pintype "bidirectional"))
      (node (ref "J8") (pin "15") (pinfunction "15_15") (pintype "bidirectional"))
      (node (ref "J8") (pin "3") (pinfunction "3_3") (pintype "bidirectional"))
      (node (ref "J8") (pin "5") (pinfunction "5_5") (pintype "bidirectional"))
      (node (ref "J8") (pin "7") (pinfunction "7_7") (pintype "bidirectional"))
      (node (ref "J8") (pin "9") (pinfunction "9_9") (pintype "bidirectional"))
      (node (ref "U11") (pin "4") (pinfunction "G2A_4") (pintype "input"))
      (node (ref "U14") (pin "4") (pinfunction "I0_4") (pintype "input"))
      (node (ref "U14") (pin "5") (pinfunction "I1_5") (pintype "input"))
    )
    (net (code "24") (name "CLK_0") (class "Default")
      (node (ref "U1") (pin "11") (pinfunction "CLK_11") (pintype "input"))
      (node (ref "U12") (pin "3") (pinfunction "O_3") (pintype "output"))
    )
    (net (code "25") (name "CLK_1") (class "Default")
      (node (ref "U12") (pin "6") (pinfunction "O_6") (pintype "output"))
      (node (ref "U2") (pin "11") (pinfunction "CLK_11") (pintype "input"))
    )
    (net (code "26") (name "CLK_2") (class "Default")
      (node (ref "U12") (pin "10") (pinfunction "O_10") (pintype "output"))
      (node (ref "U3") (pin "11") (pinfunction "CLK_11") (pintype "input"))
    )
    (net (code "27") (name "CLK_3") (class "Default")
      (node (ref "U12") (pin "13") (pinfunction "O_13") (pintype "output"))
      (node (ref "U4") (pin "11") (pinfunction "CLK_11") (pintype "input"))
    )
    (net (code "28") (name "CLK_4") (class "Default")
      (node (ref "U13") (pin "3") (pinfunction "O_3") (pintype "output"))
      (node (ref "U6") (pin "11") (pinfunction "CLK_11") (pintype "input"))
    )
    (net (code "29") (name "CLK_5") (class "Default")
      (node (ref "U13") (pin "6") (pinfunction "O_6") (pintype "output"))
      (node (ref "U7") (pin "11") (pinfunction "CLK_11") (pintype "input"))
    )
    (net (code "30") (name "CLK_6") (class "Default")
      (node (ref "U13") (pin "10") (pinfunction "O_10") (pintype "output"))
      (node (ref "U8") (pin "11") (pinfunction "CLK_11") (pintype "input"))
    )
    (net (code "31") (name "CLK_7") (class "Default")
      (node (ref "U13") (pin "13") (pinfunction "O_13") (pintype "output"))
      (node (ref "U9") (pin "11") (pinfunction "CLK_11") (pintype "input"))
    )
    (net (code "32") (name "CTRL_0") (class "Default")
      (node (ref "J5") (pin "12") (pinfunction "12_12") (pintype "bidirectional"))
      (node (ref "J7") (pin "9") (pinfunction "9_9") (pintype "bidirectional"))
      (node (ref "U11") (pin "1") (pinfunction "A_1") (pintype "input"))
      (node (ref "U16") (pin "2") (pinfunction "A1_2") (pintype "input"))
    )
    (net (code "33") (name "CTRL_1") (class "Default")
      (node (ref "J5") (pin "13") (pinfunction "13_13") (pintype "bidirectional"))
      (node (ref "J7") (pin "10") (pinfunction "10_10") (pintype "bidirectional"))
      (node (ref "U11") (pin "2") (pinfunction "B_2") (pintype "input"))
      (node (ref "U16") (pin "4") (pinfunction "A2_4") (pintype "input"))
    )
    (net (code "34") (name "CTRL_2") (class "Default")
      (node (ref "J5") (pin "14") (pinfunction "14_14") (pintype "bidirectional"))
      (node (ref "J7") (pin "11") (pinfunction "11_11") (pintype "bidirectional"))
      (node (ref "U11") (pin "3") (pinfunction "C_3") (pintype "input"))
      (node (ref "U16") (pin "6") (pinfunction "A3_6") (pintype "input"))
    )
    (net (code "35") (name "CTRL_3") (class "Default")
      (node (ref "J5") (pin "15") (pinfunction "15_15") (pintype "bidirectional"))
      (node (ref "J7") (pin "12") (pinfunction "12_12") (pintype "bidirectional"))
      (node (ref "U10") (pin "1") (pinfunction "A_1") (pintype "input"))
      (node (ref "U16") (pin "8") (pinfunction "A4_8") (pintype "input"))
    )
    (net (code "36") (name "CTRL_4") (class "Default")
      (node (ref "J5") (pin "16") (pinfunction "16_16") (pintype "bidirectional"))
      (node (ref "J7") (pin "13") (pinfunction "13_13") (pintype "bidirectional"))
      (node (ref "U10") (pin "2") (pinfunction "B_2") (pintype "input"))
      (node (ref "U16") (pin "17") (pinfunction "A1_17") (pintype "input"))
    )
    (net (code "37") (name "CTRL_5") (class "Default")
      (node (ref "J5") (pin "17") (pinfunction "17_17") (pintype "bidirectional"))
      (node (ref "J7") (pin "14") (pinfunction "14_14") (pintype "bidirectional"))
      (node (ref "U10") (pin "3") (pinfunction "C_3") (pintype "input"))
      (node (ref "U16") (pin "15") (pinfunction "A2_15") (pintype "input"))
    )
    (net (code "38") (name "CTRL_6") (class "Default")
      (node (ref "J5") (pin "18") (pinfunction "18_18") (pintype "bidirectional"))
      (node (ref "J7") (pin "15") (pinfunction "15_15") (pintype "bidirectional"))
      (node (ref "U14") (pin "1") (pinfunction "I0_1") (pintype "input"))
      (node (ref "U14") (pin "2") (pinfunction "I1_2") (pintype "input"))
      (node (ref "U16") (pin "13") (pinfunction "A3_13") (pintype "input"))
    )
    (net (code "39") (name "CTRL_7") (class "Default")
      (node (ref "J5") (pin "19") (pinfunction "19_19") (pintype "bidirectional"))
      (node (ref "J7") (pin "16") (pinfunction "16_16") (pintype "bidirectional"))
      (node (ref "U16") (pin "11") (pinfunction "A4_11") (pintype "input"))
    )
    (net (code "40") (name "GND") (class "Default")
      (node (ref "C1") (pin "K") (pinfunction "K_K") (pintype "passive"))
      (node (ref "C10") (pin "2") (pinfunction "2_2") (pintype "passive"))
      (node (ref "C11") (pin "2") (pinfunction "2_2") (pintype "passive"))
      (node (ref "C12") (pin "2") (pinfunction "2_2") (pintype "passive"))
      (node (ref "C13") (pin "2") (pinfunction "2_2") (pintype "passive"))
      (node (ref "C14") (pin "2") (pinfunction "2_2") (pintype "passive"))
      (node (ref "C15") (pin "2") (pinfunction "2_2") (pintype "passive"))
      (node (ref "C16") (pin "2") (pinfunction "2_2") (pintype "passive"))
      (node (ref "C2") (pin "2") (pinfunction "2_2") (pintype "passive"))
      (node (ref "C3") (pin "2") (pinfunction "2_2") (pintype "passive"))
      (node (ref "C4") (pin "2") (pinfunction "2_2") (pintype "passive"))
      (node (ref "C5") (pin "2") (pinfunction "2_2") (pintype "passive"))
      (node (ref "C6") (pin "2") (pinfunction "2_2") (pintype "passive"))
      (node (ref "C7") (pin "2") (pinfunction "2_2") (pintype "passive"))
      (node (ref "C8") (pin "2") (pinfunction "2_2") (pintype "passive"))
      (node (ref "C9") (pin "2") (pinfunction "2_2") (pintype "passive"))
      (node (ref "J1") (pin "1") (pinfunction "1_1") (pintype "bidirectional"))
      (node (ref "J1") (pin "10") (pinfunction "10_10") (pintype "bidirectional"))
      (node (ref "J1") (pin "11") (pinfunction "11_11") (pintype "bidirectional"))
      (node (ref "J1") (pin "20") (pinfunction "20_20") (pintype "bidirectional"))
      (node (ref "J2") (pin "1") (pinfunction "1_1") (pintype "bidirectional"))
      (node (ref "J2") (pin "10") (pinfunction "10_10") (pintype "bidirectional"))
      (node (ref "J2") (pin "11") (pinfunction "11_11") (pintype "bidirectional"))
      (node (ref "J2") (pin "20") (pinfunction "20_20") (pintype "bidirectional"))
      (node (ref "J21") (pin "1") (pinfunction "1_1") (pintype "bidirectional"))
      (node (ref "J21") (pin "10") (pinfunction "10_10") (pintype "bidirectional"))
      (node (ref "J21") (pin "11") (pinfunction "11_11") (pintype "bidirectional"))
      (node (ref "J21") (pin "20") (pinfunction "20_20") (pintype "bidirectional"))
      (node (ref "J22") (pin "1") (pinfunction "1_1") (pintype "bidirectional"))
      (node (ref "J22") (pin "10") (pinfunction "10_10") (pintype "bidirectional"))
      (node (ref "J22") (pin "11") (pinfunction "11_11") (pintype "bidirectional"))
      (node (ref "J22") (pin "20") (pinfunction "20_20") (pintype "bidirectional"))
      (node (ref "J3") (pin "1") (pinfunction "1_1") (pintype "bidirectional"))
      (node (ref "J3") (pin "10") (pinfunction "10_10") (pintype "bidirectional"))
      (node (ref "J3") (pin "11") (pinfunction "11_11") (pintype "bidirectional"))
      (node (ref "J3") (pin "20") (pinfunction "20_20") (pintype "bidirectional"))
      (node (ref "J4") (pin "1") (pinfunction "1_1") (pintype "bidirectional"))
      (node (ref "J4") (pin "10") (pinfunction "10_10") (pintype "bidirectional"))
      (node (ref "J4") (pin "11") (pinfunction "11_11") (pintype "bidirectional"))
      (node (ref "J4") (pin "20") (pinfunction "20_20") (pintype "bidirectional"))
      (node (ref "J5") (pin "1") (pinfunction "1_1") (pintype "bidirectional"))
      (node (ref "J5") (pin "10") (pinfunction "10_10") (pintype "bidirectional"))
      (node (ref "J5") (pin "11") (pinfunction "11_11") (pintype "bidirectional"))
      (node (ref "J5") (pin "20") (pinfunction "20_20") (pintype "bidirectional"))
      (node (ref "J5") (pin "21") (pinfunction "21_21") (pintype "bidirectional"))
      (node (ref "J5") (pin "30") (pinfunction "30_30") (pintype "bidirectional"))
      (node (ref "J6") (pin "1") (pinfunction "1_1") (pintype "bidirectional"))
      (node (ref "J6") (pin "10") (pinfunction "10_10") (pintype "bidirectional"))
      (node (ref "J6") (pin "11") (pinfunction "11_11") (pintype "bidirectional"))
      (node (ref "J6") (pin "20") (pinfunction "20_20") (pintype "bidirectional"))
      (node (ref "J6") (pin "21") (pinfunction "21_21") (pintype "bidirectional"))
      (node (ref "J6") (pin "30") (pinfunction "30_30") (pintype "bidirectional"))
      (node (ref "J7") (pin "49") (pinfunction "49_49") (pintype "bidirectional"))
      (node (ref "J7") (pin "50") (pinfunction "50_50") (pintype "bidirectional"))
      (node (ref "PP2") (pin "1") (pinfunction "P$1_1") (pintype "bidirectional"))
      (node (ref "TP1") (pin "P$1") (pinfunction "P$1_P$1") (pintype "bidirectional"))
      (node (ref "TP2") (pin "P$1") (pinfunction "P$1_P$1") (pintype "bidirectional"))
      (node (ref "TP3") (pin "P$1") (pinfunction "P$1_P$1") (pintype "bidirectional"))
      (node (ref "U1") (pin "1") (pinfunction "OC_1") (pintype "input"))
      (node (ref "U1") (pin "10") (pinfunction "GND_10") (pintype "power_in"))
      (node (ref "U10") (pin "4") (pinfunction "G2A_4") (pintype "input"))
      (node (ref "U10") (pin "5") (pinfunction "G2B_5") (pintype "input"))
      (node (ref "U10") (pin "8") (pinfunction "GND_8") (pintype "power_in"))
      (node (ref "U11") (pin "5") (pinfunction "G2B_5") (pintype "input"))
      (node (ref "U11") (pin "8") (pinfunction "GND_8") (pintype "power_in"))
      (node (ref "U12") (pin "7") (pinfunction "GND_7") (pintype "power_in"))
      (node (ref "U13") (pin "7") (pinfunction "GND_7") (pintype "power_in"))
      (node (ref "U14") (pin "7") (pinfunction "GND_7") (pintype "power_in"))
      (node (ref "U15") (pin "1") (pinfunction "G_1") (pintype "input"))
      (node (ref "U15") (pin "10") (pinfunction "GND_10") (pintype "power_in"))
      (node (ref "U15") (pin "19") (pinfunction "G_19") (pintype "input"))
      (node (ref "U16") (pin "1") (pinfunction "G_1") (pintype "input"))
      (node (ref "U16") (pin "10") (pinfunction "GND_10") (pintype "power_in"))
      (node (ref "U16") (pin "19") (pinfunction "G_19") (pintype "input"))
      (node (ref "U17") (pin "10") (pinfunction "GND_10") (pintype "power_in"))
      (node (ref "U2") (pin "1") (pinfunction "OC_1") (pintype "input"))
      (node (ref "U2") (pin "10") (pinfunction "GND_10") (pintype "power_in"))
      (node (ref "U3") (pin "1") (pinfunction "OC_1") (pintype "input"))
      (node (ref "U3") (pin "10") (pinfunction "GND_10") (pintype "power_in"))
      (node (ref "U4") (pin "1") (pinfunction "OC_1") (pintype "input"))
      (node (ref "U4") (pin "10") (pinfunction "GND_10") (pintype "power_in"))
      (node (ref "U46") (pin "10") (pinfunction "GND_10") (pintype "power_in"))
      (node (ref "U47") (pin "10") (pinfunction "GND_10") (pintype "power_in"))
      (node (ref "U48") (pin "10") (pinfunction "GND_10") (pintype "power_in"))
      (node (ref "U5") (pin "1") (pinfunction "G_1") (pintype "input"))
      (node (ref "U5") (pin "10") (pinfunction "GND_10") (pintype "power_in"))
      (node (ref "U5") (pin "19") (pinfunction "G_19") (pintype "input"))
      (node (ref "U50") (pin "1") (pinfunction "G_1") (pintype "input"))
      (node (ref "U50") (pin "10") (pinfunction "GND_10") (pintype "power_in"))
      (node (ref "U50") (pin "19") (pinfunction "G_19") (pintype "input"))
      (node (ref "U51") (pin "10") (pinfunction "GND_10") (pintype "power_in"))
      (node (ref "U6") (pin "1") (pinfunction "OC_1") (pintype "input"))
      (node (ref "U6") (pin "10") (pinfunction "GND_10") (pintype "power_in"))
      (node (ref "U7") (pin "1") (pinfunction "OC_1") (pintype "input"))
      (node (ref "U7") (pin "10") (pinfunction "GND_10") (pintype "power_in"))
      (node (ref "U8") (pin "1") (pinfunction "OC_1") (pintype "input"))
      (node (ref "U8") (pin "10") (pinfunction "GND_10") (pintype "power_in"))
      (node (ref "U9") (pin "1") (pinfunction "OC_1") (pintype "input"))
      (node (ref "U9") (pin "10") (pinfunction "GND_10") (pintype "power_in"))
    )
    (net (code "41") (name "IN0") (class "Default")
      (node (ref "J21") (pin "2") (pinfunction "2_2") (pintype "bidirectional"))
      (node (ref "U47") (pin "2") (pinfunction "A1_2") (pintype "input"))
    )
    (net (code "42") (name "IN1") (class "Default")
      (node (ref "J21") (pin "3") (pinfunction "3_3") (pintype "bidirectional"))
      (node (ref "U47") (pin "4") (pinfunction "A2_4") (pintype "input"))
    )
    (net (code "43") (name "IN2") (class "Default")
      (node (ref "J21") (pin "4") (pinfunction "4_4") (pintype "bidirectional"))
      (node (ref "U47") (pin "6") (pinfunction "A3_6") (pintype "input"))
    )
    (net (code "44") (name "IN3") (class "Default")
      (node (ref "J21") (pin "5") (pinfunction "5_5") (pintype "bidirectional"))
      (node (ref "U47") (pin "8") (pinfunction "A4_8") (pintype "input"))
    )
    (net (code "45") (name "IN4") (class "Default")
      (node (ref "J21") (pin "6") (pinfunction "6_6") (pintype "bidirectional"))
      (node (ref "U47") (pin "17") (pinfunction "A1_17") (pintype "input"))
    )
    (net (code "46") (name "IN5") (class "Default")
      (node (ref "J21") (pin "7") (pinfunction "7_7") (pintype "bidirectional"))
      (node (ref "U47") (pin "15") (pinfunction "A2_15") (pintype "input"))
    )
    (net (code "47") (name "IN6") (class "Default")
      (node (ref "J21") (pin "8") (pinfunction "8_8") (pintype "bidirectional"))
      (node (ref "U47") (pin "13") (pinfunction "A3_13") (pintype "input"))
    )
    (net (code "48") (name "IN7") (class "Default")
      (node (ref "J21") (pin "9") (pinfunction "9_9") (pintype "bidirectional"))
      (node (ref "U47") (pin "11") (pinfunction "A4_11") (pintype "input"))
    )
    (net (code "49") (name "IN8") (class "Default")
      (node (ref "J21") (pin "12") (pinfunction "12_12") (pintype "bidirectional"))
      (node (ref "U51") (pin "2") (pinfunction "A1_2") (pintype "input"))
    )
    (net (code "50") (name "IN9") (class "Default")
      (node (ref "J21") (pin "13") (pinfunction "13_13") (pintype "bidirectional"))
      (node (ref "U51") (pin "4") (pinfunction "A2_4") (pintype "input"))
    )
    (net (code "51") (name "IN10") (class "Default")
      (node (ref "J21") (pin "14") (pinfunction "14_14") (pintype "bidirectional"))
      (node (ref "U51") (pin "6") (pinfunction "A3_6") (pintype "input"))
    )
    (net (code "52") (name "IN11") (class "Default")
      (node (ref "J21") (pin "15") (pinfunction "15_15") (pintype "bidirectional"))
      (node (ref "U51") (pin "8") (pinfunction "A4_8") (pintype "input"))
    )
    (net (code "53") (name "IN12") (class "Default")
      (node (ref "J21") (pin "16") (pinfunction "16_16") (pintype "bidirectional"))
      (node (ref "U51") (pin "17") (pinfunction "A1_17") (pintype "input"))
    )
    (net (code "54") (name "IN13") (class "Default")
      (node (ref "J21") (pin "17") (pinfunction "17_17") (pintype "bidirectional"))
      (node (ref "U51") (pin "15") (pinfunction "A2_15") (pintype "input"))
    )
    (net (code "55") (name "IN14") (class "Default")
      (node (ref "J21") (pin "18") (pinfunction "18_18") (pintype "bidirectional"))
      (node (ref "U51") (pin "13") (pinfunction "A3_13") (pintype "input"))
    )
    (net (code "56") (name "IN15") (class "Default")
      (node (ref "J21") (pin "19") (pinfunction "19_19") (pintype "bidirectional"))
      (node (ref "U51") (pin "11") (pinfunction "A4_11") (pintype "input"))
    )
    (net (code "57") (name "IN_RD_BUS_0") (class "Default")
      (node (ref "J6") (pin "22") (pinfunction "22_22") (pintype "bidirectional"))
      (node (ref "U17") (pin "2") (pinfunction "A1_2") (pintype "input"))
    )
    (net (code "58") (name "IN_RD_BUS_1") (class "Default")
      (node (ref "J6") (pin "23") (pinfunction "23_23") (pintype "bidirectional"))
      (node (ref "U17") (pin "4") (pinfunction "A2_4") (pintype "input"))
    )
    (net (code "59") (name "IN_RD_BUS_2") (class "Default")
      (node (ref "J6") (pin "24") (pinfunction "24_24") (pintype "bidirectional"))
      (node (ref "U17") (pin "6") (pinfunction "A3_6") (pintype "input"))
    )
    (net (code "60") (name "IN_RD_BUS_3") (class "Default")
      (node (ref "J6") (pin "25") (pinfunction "25_25") (pintype "bidirectional"))
      (node (ref "U17") (pin "8") (pinfunction "A4_8") (pintype "input"))
    )
    (net (code "61") (name "IN_RD_BUS_4") (class "Default")
      (node (ref "J6") (pin "26") (pinfunction "26_26") (pintype "bidirectional"))
      (node (ref "U17") (pin "17") (pinfunction "A1_17") (pintype "input"))
    )
    (net (code "62") (name "IN_RD_BUS_5") (class "Default")
      (node (ref "J6") (pin "27") (pinfunction "27_27") (pintype "bidirectional"))
      (node (ref "U17") (pin "15") (pinfunction "A2_15") (pintype "input"))
    )
    (net (code "63") (name "IN_RD_BUS_6") (class "Default")
      (node (ref "J6") (pin "28") (pinfunction "28_28") (pintype "bidirectional"))
      (node (ref "U17") (pin "13") (pinfunction "A3_13") (pintype "input"))
    )
    (net (code "64") (name "IN_RD_BUS_7") (class "Default")
      (node (ref "J6") (pin "29") (pinfunction "29_29") (pintype "bidirectional"))
      (node (ref "U17") (pin "11") (pinfunction "A4_11") (pintype "input"))
    )
    (net (code "65") (name "Net-(U3A-1Q)") (class "Default")
      (node (ref "J2") (pin "9") (pinfunction "9_9") (pintype "bidirectional"))
      (node (ref "U3") (pin "2") (pinfunction "1Q_2") (pintype "tri_state"))
    )
    (net (code "66") (name "Net-(U3A-2Q)") (class "Default")
      (node (ref "J2") (pin "8") (pinfunction "8_8") (pintype "bidirectional"))
      (node (ref "U3") (pin "5") (pinfunction "2Q_5") (pintype "tri_state"))
    )
    (net (code "67") (name "Net-(U3A-3Q)") (class "Default")
      (node (ref "J2") (pin "7") (pinfunction "7_7") (pintype "bidirectional"))
      (node (ref "U3") (pin "6") (pinfunction "3Q_6") (pintype "tri_state"))
    )
    (net (code "68") (name "Net-(U3A-4Q)") (class "Default")
      (node (ref "J2") (pin "6") (pinfunction "6_6") (pintype "bidirectional"))
      (node (ref "U3") (pin "9") (pinfunction "4Q_9") (pintype "tri_state"))
    )
    (net (code "69") (name "Net-(U3A-5Q)") (class "Default")
      (node (ref "J2") (pin "5") (pinfunction "5_5") (pintype "bidirectional"))
      (node (ref "U3") (pin "12") (pinfunction "5Q_12") (pintype "tri_state"))
    )
    (net (code "70") (name "Net-(U3A-6Q)") (class "Default")
      (node (ref "J2") (pin "4") (pinfunction "4_4") (pintype "bidirectional"))
      (node (ref "U3") (pin "15") (pinfunction "6Q_15") (pintype "tri_state"))
    )
    (net (code "71") (name "Net-(U3A-7Q)") (class "Default")
      (node (ref "J2") (pin "3") (pinfunction "3_3") (pintype "bidirectional"))
      (node (ref "U3") (pin "16") (pinfunction "7Q_16") (pintype "tri_state"))
    )
    (net (code "72") (name "Net-(U3A-8Q)") (class "Default")
      (node (ref "J2") (pin "2") (pinfunction "2_2") (pintype "bidirectional"))
      (node (ref "U3") (pin "19") (pinfunction "8Q_19") (pintype "tri_state"))
    )
    (net (code "73") (name "Net-(U4A-1Q)") (class "Default")
      (node (ref "J2") (pin "19") (pinfunction "19_19") (pintype "bidirectional"))
      (node (ref "U4") (pin "2") (pinfunction "1Q_2") (pintype "tri_state"))
    )
    (net (code "74") (name "Net-(U4A-2Q)") (class "Default")
      (node (ref "J2") (pin "18") (pinfunction "18_18") (pintype "bidirectional"))
      (node (ref "U4") (pin "5") (pinfunction "2Q_5") (pintype "tri_state"))
    )
    (net (code "75") (name "Net-(U4A-3Q)") (class "Default")
      (node (ref "J2") (pin "17") (pinfunction "17_17") (pintype "bidirectional"))
      (node (ref "U4") (pin "6") (pinfunction "3Q_6") (pintype "tri_state"))
    )
    (net (code "76") (name "Net-(U4A-4Q)") (class "Default")
      (node (ref "J2") (pin "16") (pinfunction "16_16") (pintype "bidirectional"))
      (node (ref "U4") (pin "9") (pinfunction "4Q_9") (pintype "tri_state"))
    )
    (net (code "77") (name "Net-(U4A-5Q)") (class "Default")
      (node (ref "J2") (pin "15") (pinfunction "15_15") (pintype "bidirectional"))
      (node (ref "U4") (pin "12") (pinfunction "5Q_12") (pintype "tri_state"))
    )
    (net (code "78") (name "Net-(U4A-6Q)") (class "Default")
      (node (ref "J2") (pin "14") (pinfunction "14_14") (pintype "bidirectional"))
      (node (ref "U4") (pin "15") (pinfunction "6Q_15") (pintype "tri_state"))
    )
    (net (code "79") (name "Net-(U4A-7Q)") (class "Default")
      (node (ref "J2") (pin "13") (pinfunction "13_13") (pintype "bidirectional"))
      (node (ref "U4") (pin "16") (pinfunction "7Q_16") (pintype "tri_state"))
    )
    (net (code "80") (name "Net-(U4A-8Q)") (class "Default")
      (node (ref "J2") (pin "12") (pinfunction "12_12") (pintype "bidirectional"))
      (node (ref "U4") (pin "19") (pinfunction "8Q_19") (pintype "tri_state"))
    )
    (net (code "81") (name "Net-(U6A-1Q)") (class "Default")
      (node (ref "J3") (pin "9") (pinfunction "9_9") (pintype "bidirectional"))
      (node (ref "U6") (pin "2") (pinfunction "1Q_2") (pintype "tri_state"))
    )
    (net (code "82") (name "Net-(U6A-2Q)") (class "Default")
      (node (ref "J3") (pin "8") (pinfunction "8_8") (pintype "bidirectional"))
      (node (ref "U6") (pin "5") (pinfunction "2Q_5") (pintype "tri_state"))
    )
    (net (code "83") (name "Net-(U6A-3Q)") (class "Default")
      (node (ref "J3") (pin "7") (pinfunction "7_7") (pintype "bidirectional"))
      (node (ref "U6") (pin "6") (pinfunction "3Q_6") (pintype "tri_state"))
    )
    (net (code "84") (name "Net-(U6A-4Q)") (class "Default")
      (node (ref "J3") (pin "6") (pinfunction "6_6") (pintype "bidirectional"))
      (node (ref "U6") (pin "9") (pinfunction "4Q_9") (pintype "tri_state"))
    )
    (net (code "85") (name "Net-(U6A-5Q)") (class "Default")
      (node (ref "J3") (pin "5") (pinfunction "5_5") (pintype "bidirectional"))
      (node (ref "U6") (pin "12") (pinfunction "5Q_12") (pintype "tri_state"))
    )
    (net (code "86") (name "Net-(U6A-6Q)") (class "Default")
      (node (ref "J3") (pin "4") (pinfunction "4_4") (pintype "bidirectional"))
      (node (ref "U6") (pin "15") (pinfunction "6Q_15") (pintype "tri_state"))
    )
    (net (code "87") (name "Net-(U6A-7Q)") (class "Default")
      (node (ref "J3") (pin "3") (pinfunction "3_3") (pintype "bidirectional"))
      (node (ref "U6") (pin "16") (pinfunction "7Q_16") (pintype "tri_state"))
    )
    (net (code "88") (name "Net-(U6A-8Q)") (class "Default")
      (node (ref "J3") (pin "2") (pinfunction "2_2") (pintype "bidirectional"))
      (node (ref "U6") (pin "19") (pinfunction "8Q_19") (pintype "tri_state"))
    )
    (net (code "89") (name "Net-(U7A-1Q)") (class "Default")
      (node (ref "J3") (pin "19") (pinfunction "19_19") (pintype "bidirectional"))
      (node (ref "U7") (pin "2") (pinfunction "1Q_2") (pintype "tri_state"))
    )
    (net (code "90") (name "Net-(U7A-2Q)") (class "Default")
      (node (ref "J3") (pin "18") (pinfunction "18_18") (pintype "bidirectional"))
      (node (ref "U7") (pin "5") (pinfunction "2Q_5") (pintype "tri_state"))
    )
    (net (code "91") (name "Net-(U7A-3Q)") (class "Default")
      (node (ref "J3") (pin "17") (pinfunction "17_17") (pintype "bidirectional"))
      (node (ref "U7") (pin "6") (pinfunction "3Q_6") (pintype "tri_state"))
    )
    (net (code "92") (name "Net-(U7A-4Q)") (class "Default")
      (node (ref "J3") (pin "16") (pinfunction "16_16") (pintype "bidirectional"))
      (node (ref "U7") (pin "9") (pinfunction "4Q_9") (pintype "tri_state"))
    )
    (net (code "93") (name "Net-(U7A-5Q)") (class "Default")
      (node (ref "J3") (pin "15") (pinfunction "15_15") (pintype "bidirectional"))
      (node (ref "U7") (pin "12") (pinfunction "5Q_12") (pintype "tri_state"))
    )
    (net (code "94") (name "Net-(U7A-6Q)") (class "Default")
      (node (ref "J3") (pin "14") (pinfunction "14_14") (pintype "bidirectional"))
      (node (ref "U7") (pin "15") (pinfunction "6Q_15") (pintype "tri_state"))
    )
    (net (code "95") (name "Net-(U7A-7Q)") (class "Default")
      (node (ref "J3") (pin "13") (pinfunction "13_13") (pintype "bidirectional"))
      (node (ref "U7") (pin "16") (pinfunction "7Q_16") (pintype "tri_state"))
    )
    (net (code "96") (name "Net-(U7A-8Q)") (class "Default")
      (node (ref "J3") (pin "12") (pinfunction "12_12") (pintype "bidirectional"))
      (node (ref "U7") (pin "19") (pinfunction "8Q_19") (pintype "tri_state"))
    )
    (net (code "97") (name "Net-(U8A-1Q)") (class "Default")
      (node (ref "J4") (pin "9") (pinfunction "9_9") (pintype "bidirectional"))
      (node (ref "U8") (pin "2") (pinfunction "1Q_2") (pintype "tri_state"))
    )
    (net (code "98") (name "Net-(U8A-2Q)") (class "Default")
      (node (ref "J4") (pin "8") (pinfunction "8_8") (pintype "bidirectional"))
      (node (ref "U8") (pin "5") (pinfunction "2Q_5") (pintype "tri_state"))
    )
    (net (code "99") (name "Net-(U8A-3Q)") (class "Default")
      (node (ref "J4") (pin "7") (pinfunction "7_7") (pintype "bidirectional"))
      (node (ref "U8") (pin "6") (pinfunction "3Q_6") (pintype "tri_state"))
    )
    (net (code "100") (name "Net-(U8A-4Q)") (class "Default")
      (node (ref "J4") (pin "6") (pinfunction "6_6") (pintype "bidirectional"))
      (node (ref "U8") (pin "9") (pinfunction "4Q_9") (pintype "tri_state"))
    )
    (net (code "101") (name "Net-(U8A-5Q)") (class "Default")
      (node (ref "J4") (pin "5") (pinfunction "5_5") (pintype "bidirectional"))
      (node (ref "U8") (pin "12") (pinfunction "5Q_12") (pintype "tri_state"))
    )
    (net (code "102") (name "Net-(U8A-6Q)") (class "Default")
      (node (ref "J4") (pin "4") (pinfunction "4_4") (pintype "bidirectional"))
      (node (ref "U8") (pin "15") (pinfunction "6Q_15") (pintype "tri_state"))
    )
    (net (code "103") (name "Net-(U8A-7Q)") (class "Default")
      (node (ref "J4") (pin "3") (pinfunction "3_3") (pintype "bidirectional"))
      (node (ref "U8") (pin "16") (pinfunction "7Q_16") (pintype "tri_state"))
    )
    (net (code "104") (name "Net-(U8A-8Q)") (class "Default")
      (node (ref "J4") (pin "2") (pinfunction "2_2") (pintype "bidirectional"))
      (node (ref "U8") (pin "19") (pinfunction "8Q_19") (pintype "tri_state"))
    )
    (net (code "105") (name "Net-(U9A-1Q)") (class "Default")
      (node (ref "J4") (pin "19") (pinfunction "19_19") (pintype "bidirectional"))
      (node (ref "U9") (pin "2") (pinfunction "1Q_2") (pintype "tri_state"))
    )
    (net (code "106") (name "Net-(U9A-2Q)") (class "Default")
      (node (ref "J4") (pin "18") (pinfunction "18_18") (pintype "bidirectional"))
      (node (ref "U9") (pin "5") (pinfunction "2Q_5") (pintype "tri_state"))
    )
    (net (code "107") (name "Net-(U9A-3Q)") (class "Default")
      (node (ref "J4") (pin "17") (pinfunction "17_17") (pintype "bidirectional"))
      (node (ref "U9") (pin "6") (pinfunction "3Q_6") (pintype "tri_state"))
    )
    (net (code "108") (name "Net-(U9A-4Q)") (class "Default")
      (node (ref "J4") (pin "16") (pinfunction "16_16") (pintype "bidirectional"))
      (node (ref "U9") (pin "9") (pinfunction "4Q_9") (pintype "tri_state"))
    )
    (net (code "109") (name "Net-(U9A-5Q)") (class "Default")
      (node (ref "J4") (pin "15") (pinfunction "15_15") (pintype "bidirectional"))
      (node (ref "U9") (pin "12") (pinfunction "5Q_12") (pintype "tri_state"))
    )
    (net (code "110") (name "Net-(U9A-6Q)") (class "Default")
      (node (ref "J4") (pin "14") (pinfunction "14_14") (pintype "bidirectional"))
      (node (ref "U9") (pin "15") (pinfunction "6Q_15") (pintype "tri_state"))
    )
    (net (code "111") (name "Net-(U9A-7Q)") (class "Default")
      (node (ref "J4") (pin "13") (pinfunction "13_13") (pintype "bidirectional"))
      (node (ref "U9") (pin "16") (pinfunction "7Q_16") (pintype "tri_state"))
    )
    (net (code "112") (name "Net-(U9A-8Q)") (class "Default")
      (node (ref "J4") (pin "12") (pinfunction "12_12") (pintype "bidirectional"))
      (node (ref "U9") (pin "19") (pinfunction "8Q_19") (pintype "tri_state"))
    )
    (net (code "113") (name "Net-(U10A-G1)") (class "Default")
      (node (ref "R2") (pin "1") (pinfunction "1_1") (pintype "passive"))
      (node (ref "U10") (pin "6") (pinfunction "G1_6") (pintype "input"))
      (node (ref "U14") (pin "11") (pinfunction "I0_11") (pintype "input"))
      (node (ref "U14") (pin "12") (pinfunction "I1_12") (pintype "input"))
      (node (ref "U14") (pin "8") (pinfunction "I0_8") (pintype "input"))
      (node (ref "U14") (pin "9") (pinfunction "I1_9") (pintype "input"))
    )
    (net (code "114") (name "Net-(U10A-Y0)") (class "Default")
      (node (ref "J8") (pin "16") (pinfunction "16_16") (pintype "bidirectional"))
      (node (ref "U10") (pin "15") (pinfunction "Y0_15") (pintype "output"))
    )
    (net (code "115") (name "Net-(U10A-Y1)") (class "Default")
      (node (ref "J8") (pin "14") (pinfunction "14_14") (pintype "bidirectional"))
      (node (ref "U10") (pin "14") (pinfunction "Y1_14") (pintype "output"))
    )
    (net (code "116") (name "Net-(U10A-Y2)") (class "Default")
      (node (ref "J8") (pin "12") (pinfunction "12_12") (pintype "bidirectional"))
      (node (ref "U10") (pin "13") (pinfunction "Y2_13") (pintype "output"))
    )
    (net (code "117") (name "Net-(U10A-Y3)") (class "Default")
      (node (ref "J8") (pin "10") (pinfunction "10_10") (pintype "bidirectional"))
      (node (ref "U10") (pin "12") (pinfunction "Y3_12") (pintype "output"))
    )
    (net (code "118") (name "Net-(U10A-Y4)") (class "Default")
      (node (ref "J8") (pin "8") (pinfunction "8_8") (pintype "bidirectional"))
      (node (ref "U10") (pin "11") (pinfunction "Y4_11") (pintype "output"))
    )
    (net (code "119") (name "Net-(U10A-Y5)") (class "Default")
      (node (ref "J8") (pin "6") (pinfunction "6_6") (pintype "bidirectional"))
      (node (ref "U10") (pin "10") (pinfunction "Y5_10") (pintype "output"))
    )
    (net (code "120") (name "Net-(U10A-Y6)") (class "Default")
      (node (ref "J8") (pin "4") (pinfunction "4_4") (pintype "bidirectional"))
      (node (ref "U10") (pin "9") (pinfunction "Y6_9") (pintype "output"))
    )
    (net (code "121") (name "Net-(U10A-Y7)") (class "Default")
      (node (ref "J8") (pin "2") (pinfunction "2_2") (pintype "bidirectional"))
      (node (ref "U10") (pin "7") (pinfunction "Y7_7") (pintype "output"))
    )
    (net (code "122") (name "Net-(U11A-G1)") (class "Default")
      (node (ref "R1") (pin "1") (pinfunction "1_1") (pintype "passive"))
      (node (ref "U11") (pin "6") (pinfunction "G1_6") (pintype "input"))
    )
    (net (code "123") (name "Net-(U11A-Y4)") (class "Default")
      (node (ref "U11") (pin "11") (pinfunction "Y4_11") (pintype "output"))
      (node (ref "U13") (pin "2") (pinfunction "I1_2") (pintype "input"))
    )
    (net (code "124") (name "Net-(U11A-Y5)") (class "Default")
      (node (ref "U11") (pin "10") (pinfunction "Y5_10") (pintype "output"))
      (node (ref "U13") (pin "5") (pinfunction "I1_5") (pintype "input"))
    )
    (net (code "125") (name "Net-(U11A-Y6)") (class "Default")
      (node (ref "U11") (pin "9") (pinfunction "Y6_9") (pintype "output"))
      (node (ref "U13") (pin "9") (pinfunction "I1_9") (pintype "input"))
    )
    (net (code "126") (name "Net-(U11A-Y7)") (class "Default")
      (node (ref "U11") (pin "7") (pinfunction "Y7_7") (pintype "output"))
      (node (ref "U13") (pin "12") (pinfunction "I1_12") (pintype "input"))
    )
    (net (code "127") (name "Net-(U12A-I0)") (class "Default")
      (node (ref "U12") (pin "1") (pinfunction "I0_1") (pintype "input"))
      (node (ref "U12") (pin "11") (pinfunction "I0_11") (pintype "input"))
      (node (ref "U12") (pin "4") (pinfunction "I0_4") (pintype "input"))
      (node (ref "U12") (pin "8") (pinfunction "I0_8") (pintype "input"))
      (node (ref "U13") (pin "1") (pinfunction "I0_1") (pintype "input"))
      (node (ref "U13") (pin "11") (pinfunction "I0_11") (pintype "input"))
      (node (ref "U13") (pin "4") (pinfunction "I0_4") (pintype "input"))
      (node (ref "U13") (pin "8") (pinfunction "I0_8") (pintype "input"))
      (node (ref "U14") (pin "3") (pinfunction "O_3") (pintype "output"))
    )
    (net (code "128") (name "Net-(U46A-A1)") (class "Default")
      (node (ref "J22") (pin "2") (pinfunction "2_2") (pintype "bidirectional"))
      (node (ref "U46") (pin "2") (pinfunction "A1_2") (pintype "input"))
    )
    (net (code "129") (name "Net-(U46A-A2)") (class "Default")
      (node (ref "J22") (pin "3") (pinfunction "3_3") (pintype "bidirectional"))
      (node (ref "U46") (pin "4") (pinfunction "A2_4") (pintype "input"))
    )
    (net (code "130") (name "Net-(U46A-A3)") (class "Default")
      (node (ref "J22") (pin "4") (pinfunction "4_4") (pintype "bidirectional"))
      (node (ref "U46") (pin "6") (pinfunction "A3_6") (pintype "input"))
    )
    (net (code "131") (name "Net-(U46A-A4)") (class "Default")
      (node (ref "J22") (pin "5") (pinfunction "5_5") (pintype "bidirectional"))
      (node (ref "U46") (pin "8") (pinfunction "A4_8") (pintype "input"))
    )
    (net (code "132") (name "Net-(U46B-A1)") (class "Default")
      (node (ref "J22") (pin "6") (pinfunction "6_6") (pintype "bidirectional"))
      (node (ref "U46") (pin "17") (pinfunction "A1_17") (pintype "input"))
    )
    (net (code "133") (name "Net-(U46B-A2)") (class "Default")
      (node (ref "J22") (pin "7") (pinfunction "7_7") (pintype "bidirectional"))
      (node (ref "U46") (pin "15") (pinfunction "A2_15") (pintype "input"))
    )
    (net (code "134") (name "Net-(U46B-A3)") (class "Default")
      (node (ref "J22") (pin "8") (pinfunction "8_8") (pintype "bidirectional"))
      (node (ref "U46") (pin "13") (pinfunction "A3_13") (pintype "input"))
    )
    (net (code "135") (name "Net-(U46B-A4)") (class "Default")
      (node (ref "J22") (pin "9") (pinfunction "9_9") (pintype "bidirectional"))
      (node (ref "U46") (pin "11") (pinfunction "A4_11") (pintype "input"))
    )
    (net (code "136") (name "Net-(U48A-A1)") (class "Default")
      (node (ref "J22") (pin "12") (pinfunction "12_12") (pintype "bidirectional"))
      (node (ref "U48") (pin "2") (pinfunction "A1_2") (pintype "input"))
    )
    (net (code "137") (name "Net-(U48A-A2)") (class "Default")
      (node (ref "J22") (pin "13") (pinfunction "13_13") (pintype "bidirectional"))
      (node (ref "U48") (pin "4") (pinfunction "A2_4") (pintype "input"))
    )
    (net (code "138") (name "Net-(U48A-A3)") (class "Default")
      (node (ref "J22") (pin "14") (pinfunction "14_14") (pintype "bidirectional"))
      (node (ref "U48") (pin "6") (pinfunction "A3_6") (pintype "input"))
    )
    (net (code "139") (name "Net-(U48A-A4)") (class "Default")
      (node (ref "J22") (pin "15") (pinfunction "15_15") (pintype "bidirectional"))
      (node (ref "U48") (pin "8") (pinfunction "A4_8") (pintype "input"))
    )
    (net (code "140") (name "Net-(U48B-A1)") (class "Default")
      (node (ref "J22") (pin "16") (pinfunction "16_16") (pintype "bidirectional"))
      (node (ref "U48") (pin "17") (pinfunction "A1_17") (pintype "input"))
    )
    (net (code "141") (name "Net-(U48B-A2)") (class "Default")
      (node (ref "J22") (pin "17") (pinfunction "17_17") (pintype "bidirectional"))
      (node (ref "U48") (pin "15") (pinfunction "A2_15") (pintype "input"))
    )
    (net (code "142") (name "Net-(U48B-A3)") (class "Default")
      (node (ref "J22") (pin "18") (pinfunction "18_18") (pintype "bidirectional"))
      (node (ref "U48") (pin "13") (pinfunction "A3_13") (pintype "input"))
    )
    (net (code "143") (name "Net-(U48B-A4)") (class "Default")
      (node (ref "J22") (pin "19") (pinfunction "19_19") (pintype "bidirectional"))
      (node (ref "U48") (pin "11") (pinfunction "A4_11") (pintype "input"))
    )
    (net (code "144") (name "OUT0") (class "Default")
      (node (ref "J1") (pin "2") (pinfunction "2_2") (pintype "bidirectional"))
      (node (ref "U1") (pin "19") (pinfunction "8Q_19") (pintype "tri_state"))
    )
    (net (code "145") (name "OUT1") (class "Default")
      (node (ref "J1") (pin "3") (pinfunction "3_3") (pintype "bidirectional"))
      (node (ref "U1") (pin "16") (pinfunction "7Q_16") (pintype "tri_state"))
    )
    (net (code "146") (name "OUT2") (class "Default")
      (node (ref "J1") (pin "4") (pinfunction "4_4") (pintype "bidirectional"))
      (node (ref "U1") (pin "15") (pinfunction "6Q_15") (pintype "tri_state"))
    )
    (net (code "147") (name "OUT3") (class "Default")
      (node (ref "J1") (pin "5") (pinfunction "5_5") (pintype "bidirectional"))
      (node (ref "U1") (pin "12") (pinfunction "5Q_12") (pintype "tri_state"))
    )
    (net (code "148") (name "OUT4") (class "Default")
      (node (ref "J1") (pin "6") (pinfunction "6_6") (pintype "bidirectional"))
      (node (ref "U1") (pin "9") (pinfunction "4Q_9") (pintype "tri_state"))
    )
    (net (code "149") (name "OUT5") (class "Default")
      (node (ref "J1") (pin "7") (pinfunction "7_7") (pintype "bidirectional"))
      (node (ref "U1") (pin "6") (pinfunction "3Q_6") (pintype "tri_state"))
    )
    (net (code "150") (name "OUT6") (class "Default")
      (node (ref "J1") (pin "8") (pinfunction "8_8") (pintype "bidirectional"))
      (node (ref "U1") (pin "5") (pinfunction "2Q_5") (pintype "tri_state"))
    )
    (net (code "151") (name "OUT7") (class "Default")
      (node (ref "J1") (pin "9") (pinfunction "9_9") (pintype "bidirectional"))
      (node (ref "U1") (pin "2") (pinfunction "1Q_2") (pintype "tri_state"))
    )
    (net (code "152") (name "OUT8") (class "Default")
      (node (ref "J1") (pin "12") (pinfunction "12_12") (pintype "bidirectional"))
      (node (ref "U2") (pin "19") (pinfunction "8Q_19") (pintype "tri_state"))
    )
    (net (code "153") (name "OUT9") (class "Default")
      (node (ref "J1") (pin "13") (pinfunction "13_13") (pintype "bidirectional"))
      (node (ref "U2") (pin "16") (pinfunction "7Q_16") (pintype "tri_state"))
    )
    (net (code "154") (name "OUT10") (class "Default")
      (node (ref "J1") (pin "14") (pinfunction "14_14") (pintype "bidirectional"))
      (node (ref "U2") (pin "15") (pinfunction "6Q_15") (pintype "tri_state"))
    )
    (net (code "155") (name "OUT11") (class "Default")
      (node (ref "J1") (pin "15") (pinfunction "15_15") (pintype "bidirectional"))
      (node (ref "U2") (pin "12") (pinfunction "5Q_12") (pintype "tri_state"))
    )
    (net (code "156") (name "OUT12") (class "Default")
      (node (ref "J1") (pin "16") (pinfunction "16_16") (pintype "bidirectional"))
      (node (ref "U2") (pin "9") (pinfunction "4Q_9") (pintype "tri_state"))
    )
    (net (code "157") (name "OUT13") (class "Default")
      (node (ref "J1") (pin "17") (pinfunction "17_17") (pintype "bidirectional"))
      (node (ref "U2") (pin "6") (pinfunction "3Q_6") (pintype "tri_state"))
    )
    (net (code "158") (name "OUT14") (class "Default")
      (node (ref "J1") (pin "18") (pinfunction "18_18") (pintype "bidirectional"))
      (node (ref "U2") (pin "5") (pinfunction "2Q_5") (pintype "tri_state"))
    )
    (net (code "159") (name "OUT15") (class "Default")
      (node (ref "J1") (pin "19") (pinfunction "19_19") (pintype "bidirectional"))
      (node (ref "U2") (pin "2") (pinfunction "1Q_2") (pintype "tri_state"))
    )
    (net (code "160") (name "RD_BUS_0") (class "Default")
      (node (ref "J5") (pin "22") (pinfunction "22_22") (pintype "bidirectional"))
      (node (ref "J7") (pin "17") (pinfunction "17_17") (pintype "bidirectional"))
      (node (ref "U50") (pin "9") (pinfunction "Y4_9") (pintype "tri_state"))
    )
    (net (code "161") (name "RD_BUS_0_0") (class "Default")
      (node (ref "U17") (pin "18") (pinfunction "Y1_18") (pintype "tri_state"))
      (node (ref "U46") (pin "18") (pinfunction "Y1_18") (pintype "tri_state"))
      (node (ref "U47") (pin "18") (pinfunction "Y1_18") (pintype "tri_state"))
      (node (ref "U48") (pin "18") (pinfunction "Y1_18") (pintype "tri_state"))
      (node (ref "U50") (pin "11") (pinfunction "A4_11") (pintype "input"))
      (node (ref "U51") (pin "18") (pinfunction "Y1_18") (pintype "tri_state"))
    )
    (net (code "162") (name "RD_BUS_0_1") (class "Default")
      (node (ref "U17") (pin "16") (pinfunction "Y2_16") (pintype "tri_state"))
      (node (ref "U46") (pin "16") (pinfunction "Y2_16") (pintype "tri_state"))
      (node (ref "U47") (pin "16") (pinfunction "Y2_16") (pintype "tri_state"))
      (node (ref "U48") (pin "16") (pinfunction "Y2_16") (pintype "tri_state"))
      (node (ref "U50") (pin "13") (pinfunction "A3_13") (pintype "input"))
      (node (ref "U51") (pin "16") (pinfunction "Y2_16") (pintype "tri_state"))
    )
    (net (code "163") (name "RD_BUS_0_2") (class "Default")
      (node (ref "U17") (pin "14") (pinfunction "Y3_14") (pintype "tri_state"))
      (node (ref "U46") (pin "14") (pinfunction "Y3_14") (pintype "tri_state"))
      (node (ref "U47") (pin "14") (pinfunction "Y3_14") (pintype "tri_state"))
      (node (ref "U48") (pin "14") (pinfunction "Y3_14") (pintype "tri_state"))
      (node (ref "U50") (pin "15") (pinfunction "A2_15") (pintype "input"))
      (node (ref "U51") (pin "14") (pinfunction "Y3_14") (pintype "tri_state"))
    )
    (net (code "164") (name "RD_BUS_0_3") (class "Default")
      (node (ref "U17") (pin "12") (pinfunction "Y4_12") (pintype "tri_state"))
      (node (ref "U46") (pin "12") (pinfunction "Y4_12") (pintype "tri_state"))
      (node (ref "U47") (pin "12") (pinfunction "Y4_12") (pintype "tri_state"))
      (node (ref "U48") (pin "12") (pinfunction "Y4_12") (pintype "tri_state"))
      (node (ref "U50") (pin "17") (pinfunction "A1_17") (pintype "input"))
      (node (ref "U51") (pin "12") (pinfunction "Y4_12") (pintype "tri_state"))
    )
    (net (code "165") (name "RD_BUS_0_4") (class "Default")
      (node (ref "U17") (pin "3") (pinfunction "Y1_3") (pintype "tri_state"))
      (node (ref "U46") (pin "3") (pinfunction "Y1_3") (pintype "tri_state"))
      (node (ref "U47") (pin "3") (pinfunction "Y1_3") (pintype "tri_state"))
      (node (ref "U48") (pin "3") (pinfunction "Y1_3") (pintype "tri_state"))
      (node (ref "U50") (pin "8") (pinfunction "A4_8") (pintype "input"))
      (node (ref "U51") (pin "3") (pinfunction "Y1_3") (pintype "tri_state"))
    )
    (net (code "166") (name "RD_BUS_0_5") (class "Default")
      (node (ref "U17") (pin "5") (pinfunction "Y2_5") (pintype "tri_state"))
      (node (ref "U46") (pin "5") (pinfunction "Y2_5") (pintype "tri_state"))
      (node (ref "U47") (pin "5") (pinfunction "Y2_5") (pintype "tri_state"))
      (node (ref "U48") (pin "5") (pinfunction "Y2_5") (pintype "tri_state"))
      (node (ref "U50") (pin "6") (pinfunction "A3_6") (pintype "input"))
      (node (ref "U51") (pin "5") (pinfunction "Y2_5") (pintype "tri_state"))
    )
    (net (code "167") (name "RD_BUS_0_6") (class "Default")
      (node (ref "U17") (pin "7") (pinfunction "Y3_7") (pintype "tri_state"))
      (node (ref "U46") (pin "7") (pinfunction "Y3_7") (pintype "tri_state"))
      (node (ref "U47") (pin "7") (pinfunction "Y3_7") (pintype "tri_state"))
      (node (ref "U48") (pin "7") (pinfunction "Y3_7") (pintype "tri_state"))
      (node (ref "U50") (pin "4") (pinfunction "A2_4") (pintype "input"))
      (node (ref "U51") (pin "7") (pinfunction "Y3_7") (pintype "tri_state"))
    )
    (net (code "168") (name "RD_BUS_0_7") (class "Default")
      (node (ref "U17") (pin "9") (pinfunction "Y4_9") (pintype "tri_state"))
      (node (ref "U46") (pin "9") (pinfunction "Y4_9") (pintype "tri_state"))
      (node (ref "U47") (pin "9") (pinfunction "Y4_9") (pintype "tri_state"))
      (node (ref "U48") (pin "9") (pinfunction "Y4_9") (pintype "tri_state"))
      (node (ref "U50") (pin "2") (pinfunction "A1_2") (pintype "input"))
      (node (ref "U51") (pin "9") (pinfunction "Y4_9") (pintype "tri_state"))
    )
    (net (code "169") (name "RD_BUS_1") (class "Default")
      (node (ref "J5") (pin "23") (pinfunction "23_23") (pintype "bidirectional"))
      (node (ref "J7") (pin "18") (pinfunction "18_18") (pintype "bidirectional"))
      (node (ref "U50") (pin "7") (pinfunction "Y3_7") (pintype "tri_state"))
    )
    (net (code "170") (name "RD_BUS_2") (class "Default")
      (node (ref "J5") (pin "24") (pinfunction "24_24") (pintype "bidirectional"))
      (node (ref "J7") (pin "19") (pinfunction "19_19") (pintype "bidirectional"))
      (node (ref "U50") (pin "5") (pinfunction "Y2_5") (pintype "tri_state"))
    )
    (net (code "171") (name "RD_BUS_3") (class "Default")
      (node (ref "J5") (pin "25") (pinfunction "25_25") (pintype "bidirectional"))
      (node (ref "J7") (pin "20") (pinfunction "20_20") (pintype "bidirectional"))
      (node (ref "U50") (pin "3") (pinfunction "Y1_3") (pintype "tri_state"))
    )
    (net (code "172") (name "RD_BUS_4") (class "Default")
      (node (ref "J5") (pin "26") (pinfunction "26_26") (pintype "bidirectional"))
      (node (ref "J7") (pin "21") (pinfunction "21_21") (pintype "bidirectional"))
      (node (ref "U50") (pin "12") (pinfunction "Y4_12") (pintype "tri_state"))
    )
    (net (code "173") (name "RD_BUS_5") (class "Default")
      (node (ref "J5") (pin "27") (pinfunction "27_27") (pintype "bidirectional"))
      (node (ref "J7") (pin "22") (pinfunction "22_22") (pintype "bidirectional"))
      (node (ref "U50") (pin "14") (pinfunction "Y3_14") (pintype "tri_state"))
    )
    (net (code "174") (name "RD_BUS_6") (class "Default")
      (node (ref "J5") (pin "28") (pinfunction "28_28") (pintype "bidirectional"))
      (node (ref "J7") (pin "23") (pinfunction "23_23") (pintype "bidirectional"))
      (node (ref "U50") (pin "16") (pinfunction "Y2_16") (pintype "tri_state"))
    )
    (net (code "175") (name "RD_BUS_7") (class "Default")
      (node (ref "J5") (pin "29") (pinfunction "29_29") (pintype "bidirectional"))
      (node (ref "J7") (pin "24") (pinfunction "24_24") (pintype "bidirectional"))
      (node (ref "U50") (pin "18") (pinfunction "Y1_18") (pintype "tri_state"))
    )
    (net (code "176") (name "WR_BUS_0") (class "Default")
      (node (ref "J5") (pin "2") (pinfunction "2_2") (pintype "bidirectional"))
      (node (ref "J7") (pin "1") (pinfunction "1_1") (pintype "bidirectional"))
      (node (ref "U15") (pin "2") (pinfunction "A1_2") (pintype "input"))
      (node (ref "U5") (pin "11") (pinfunction "A4_11") (pintype "input"))
    )
    (net (code "177") (name "WR_BUS_0_0") (class "Default")
      (node (ref "U1") (pin "18") (pinfunction "8D_18") (pintype "input"))
      (node (ref "U2") (pin "18") (pinfunction "8D_18") (pintype "input"))
      (node (ref "U3") (pin "18") (pinfunction "8D_18") (pintype "input"))
      (node (ref "U4") (pin "18") (pinfunction "8D_18") (pintype "input"))
      (node (ref "U5") (pin "9") (pinfunction "Y4_9") (pintype "tri_state"))
      (node (ref "U6") (pin "18") (pinfunction "8D_18") (pintype "input"))
      (node (ref "U7") (pin "18") (pinfunction "8D_18") (pintype "input"))
      (node (ref "U8") (pin "18") (pinfunction "8D_18") (pintype "input"))
      (node (ref "U9") (pin "18") (pinfunction "8D_18") (pintype "input"))
    )
    (net (code "178") (name "WR_BUS_0_1") (class "Default")
      (node (ref "U1") (pin "17") (pinfunction "7D_17") (pintype "input"))
      (node (ref "U2") (pin "17") (pinfunction "7D_17") (pintype "input"))
      (node (ref "U3") (pin "17") (pinfunction "7D_17") (pintype "input"))
      (node (ref "U4") (pin "17") (pinfunction "7D_17") (pintype "input"))
      (node (ref "U5") (pin "7") (pinfunction "Y3_7") (pintype "tri_state"))
      (node (ref "U6") (pin "17") (pinfunction "7D_17") (pintype "input"))
      (node (ref "U7") (pin "17") (pinfunction "7D_17") (pintype "input"))
      (node (ref "U8") (pin "17") (pinfunction "7D_17") (pintype "input"))
      (node (ref "U9") (pin "17") (pinfunction "7D_17") (pintype "input"))
    )
    (net (code "179") (name "WR_BUS_0_2") (class "Default")
      (node (ref "U1") (pin "14") (pinfunction "6D_14") (pintype "input"))
      (node (ref "U2") (pin "14") (pinfunction "6D_14") (pintype "input"))
      (node (ref "U3") (pin "14") (pinfunction "6D_14") (pintype "input"))
      (node (ref "U4") (pin "14") (pinfunction "6D_14") (pintype "input"))
      (node (ref "U5") (pin "5") (pinfunction "Y2_5") (pintype "tri_state"))
      (node (ref "U6") (pin "14") (pinfunction "6D_14") (pintype "input"))
      (node (ref "U7") (pin "14") (pinfunction "6D_14") (pintype "input"))
      (node (ref "U8") (pin "14") (pinfunction "6D_14") (pintype "input"))
      (node (ref "U9") (pin "14") (pinfunction "6D_14") (pintype "input"))
    )
    (net (code "180") (name "WR_BUS_0_3") (class "Default")
      (node (ref "U1") (pin "13") (pinfunction "5D_13") (pintype "input"))
      (node (ref "U2") (pin "13") (pinfunction "5D_13") (pintype "input"))
      (node (ref "U3") (pin "13") (pinfunction "5D_13") (pintype "input"))
      (node (ref "U4") (pin "13") (pinfunction "5D_13") (pintype "input"))
      (node (ref "U5") (pin "3") (pinfunction "Y1_3") (pintype "tri_state"))
      (node (ref "U6") (pin "13") (pinfunction "5D_13") (pintype "input"))
      (node (ref "U7") (pin "13") (pinfunction "5D_13") (pintype "input"))
      (node (ref "U8") (pin "13") (pinfunction "5D_13") (pintype "input"))
      (node (ref "U9") (pin "13") (pinfunction "5D_13") (pintype "input"))
    )
    (net (code "181") (name "WR_BUS_0_4") (class "Default")
      (node (ref "U1") (pin "8") (pinfunction "4D_8") (pintype "input"))
      (node (ref "U2") (pin "8") (pinfunction "4D_8") (pintype "input"))
      (node (ref "U3") (pin "8") (pinfunction "4D_8") (pintype "input"))
      (node (ref "U4") (pin "8") (pinfunction "4D_8") (pintype "input"))
      (node (ref "U5") (pin "12") (pinfunction "Y4_12") (pintype "tri_state"))
      (node (ref "U6") (pin "8") (pinfunction "4D_8") (pintype "input"))
      (node (ref "U7") (pin "8") (pinfunction "4D_8") (pintype "input"))
      (node (ref "U8") (pin "8") (pinfunction "4D_8") (pintype "input"))
      (node (ref "U9") (pin "8") (pinfunction "4D_8") (pintype "input"))
    )
    (net (code "182") (name "WR_BUS_0_5") (class "Default")
      (node (ref "U1") (pin "7") (pinfunction "3D_7") (pintype "input"))
      (node (ref "U2") (pin "7") (pinfunction "3D_7") (pintype "input"))
      (node (ref "U3") (pin "7") (pinfunction "3D_7") (pintype "input"))
      (node (ref "U4") (pin "7") (pinfunction "3D_7") (pintype "input"))
      (node (ref "U5") (pin "14") (pinfunction "Y3_14") (pintype "tri_state"))
      (node (ref "U6") (pin "7") (pinfunction "3D_7") (pintype "input"))
      (node (ref "U7") (pin "7") (pinfunction "3D_7") (pintype "input"))
      (node (ref "U8") (pin "7") (pinfunction "3D_7") (pintype "input"))
      (node (ref "U9") (pin "7") (pinfunction "3D_7") (pintype "input"))
    )
    (net (code "183") (name "WR_BUS_0_6") (class "Default")
      (node (ref "U1") (pin "4") (pinfunction "2D_4") (pintype "input"))
      (node (ref "U2") (pin "4") (pinfunction "2D_4") (pintype "input"))
      (node (ref "U3") (pin "4") (pinfunction "2D_4") (pintype "input"))
      (node (ref "U4") (pin "4") (pinfunction "2D_4") (pintype "input"))
      (node (ref "U5") (pin "16") (pinfunction "Y2_16") (pintype "tri_state"))
      (node (ref "U6") (pin "4") (pinfunction "2D_4") (pintype "input"))
      (node (ref "U7") (pin "4") (pinfunction "2D_4") (pintype "input"))
      (node (ref "U8") (pin "4") (pinfunction "2D_4") (pintype "input"))
      (node (ref "U9") (pin "4") (pinfunction "2D_4") (pintype "input"))
    )
    (net (code "184") (name "WR_BUS_0_7") (class "Default")
      (node (ref "U1") (pin "3") (pinfunction "1D_3") (pintype "input"))
      (node (ref "U2") (pin "3") (pinfunction "1D_3") (pintype "input"))
      (node (ref "U3") (pin "3") (pinfunction "1D_3") (pintype "input"))
      (node (ref "U4") (pin "3") (pinfunction "1D_3") (pintype "input"))
      (node (ref "U5") (pin "18") (pinfunction "Y1_18") (pintype "tri_state"))
      (node (ref "U6") (pin "3") (pinfunction "1D_3") (pintype "input"))
      (node (ref "U7") (pin "3") (pinfunction "1D_3") (pintype "input"))
      (node (ref "U8") (pin "3") (pinfunction "1D_3") (pintype "input"))
      (node (ref "U9") (pin "3") (pinfunction "1D_3") (pintype "input"))
    )
    (net (code "185") (name "WR_BUS_1") (class "Default")
      (node (ref "J5") (pin "3") (pinfunction "3_3") (pintype "bidirectional"))
      (node (ref "J7") (pin "2") (pinfunction "2_2") (pintype "bidirectional"))
      (node (ref "U15") (pin "4") (pinfunction "A2_4") (pintype "input"))
      (node (ref "U5") (pin "13") (pinfunction "A3_13") (pintype "input"))
    )
    (net (code "186") (name "WR_BUS_2") (class "Default")
      (node (ref "J5") (pin "4") (pinfunction "4_4") (pintype "bidirectional"))
      (node (ref "J7") (pin "3") (pinfunction "3_3") (pintype "bidirectional"))
      (node (ref "U15") (pin "6") (pinfunction "A3_6") (pintype "input"))
      (node (ref "U5") (pin "15") (pinfunction "A2_15") (pintype "input"))
    )
    (net (code "187") (name "WR_BUS_3") (class "Default")
      (node (ref "J5") (pin "5") (pinfunction "5_5") (pintype "bidirectional"))
      (node (ref "J7") (pin "4") (pinfunction "4_4") (pintype "bidirectional"))
      (node (ref "U15") (pin "8") (pinfunction "A4_8") (pintype "input"))
      (node (ref "U5") (pin "17") (pinfunction "A1_17") (pintype "input"))
    )
    (net (code "188") (name "WR_BUS_4") (class "Default")
      (node (ref "J5") (pin "6") (pinfunction "6_6") (pintype "bidirectional"))
      (node (ref "J7") (pin "5") (pinfunction "5_5") (pintype "bidirectional"))
      (node (ref "U15") (pin "17") (pinfunction "A1_17") (pintype "input"))
      (node (ref "U5") (pin "8") (pinfunction "A4_8") (pintype "input"))
    )
    (net (code "189") (name "WR_BUS_5") (class "Default")
      (node (ref "J5") (pin "7") (pinfunction "7_7") (pintype "bidirectional"))
      (node (ref "J7") (pin "6") (pinfunction "6_6") (pintype "bidirectional"))
      (node (ref "U15") (pin "15") (pinfunction "A2_15") (pintype "input"))
      (node (ref "U5") (pin "6") (pinfunction "A3_6") (pintype "input"))
    )
    (net (code "190") (name "WR_BUS_6") (class "Default")
      (node (ref "J5") (pin "8") (pinfunction "8_8") (pintype "bidirectional"))
      (node (ref "J7") (pin "7") (pinfunction "7_7") (pintype "bidirectional"))
      (node (ref "U15") (pin "13") (pinfunction "A3_13") (pintype "input"))
      (node (ref "U5") (pin "4") (pinfunction "A2_4") (pintype "input"))
    )
    (net (code "191") (name "WR_BUS_7") (class "Default")
      (node (ref "J5") (pin "9") (pinfunction "9_9") (pintype "bidirectional"))
      (node (ref "J7") (pin "8") (pinfunction "8_8") (pintype "bidirectional"))
      (node (ref "U15") (pin "11") (pinfunction "A4_11") (pintype "input"))
      (node (ref "U5") (pin "2") (pinfunction "A1_2") (pintype "input"))
    )
    (net (code "192") (name "unconnected-(J7-Pad25)") (class "Default")
      (node (ref "J7") (pin "25") (pinfunction "25_25") (pintype "bidirectional"))
    )
    (net (code "193") (name "unconnected-(J7-Pad26)") (class "Default")
      (node (ref "J7") (pin "26") (pinfunction "26_26") (pintype "bidirectional"))
    )
    (net (code "194") (name "unconnected-(J7-Pad27)") (class "Default")
      (node (ref "J7") (pin "27") (pinfunction "27_27") (pintype "bidirectional"))
    )
    (net (code "195") (name "unconnected-(J7-Pad28)") (class "Default")
      (node (ref "J7") (pin "28") (pinfunction "28_28") (pintype "bidirectional"))
    )
    (net (code "196") (name "unconnected-(J7-Pad29)") (class "Default")
      (node (ref "J7") (pin "29") (pinfunction "29_29") (pintype "bidirectional"))
    )
    (net (code "197") (name "unconnected-(J7-Pad30)") (class "Default")
      (node (ref "J7") (pin "30") (pinfunction "30_30") (pintype "bidirectional"))
    )
    (net (code "198") (name "unconnected-(J7-Pad31)") (class "Default")
      (node (ref "J7") (pin "31") (pinfunction "31_31") (pintype "bidirectional"))
    )
    (net (code "199") (name "unconnected-(J7-Pad32)") (class "Default")
      (node (ref "J7") (pin "32") (pinfunction "32_32") (pintype "bidirectional"))
    )
    (net (code "200") (name "unconnected-(J7-Pad33)") (class "Default")
      (node (ref "J7") (pin "33") (pinfunction "33_33") (pintype "bidirectional"))
    )
    (net (code "201") (name "unconnected-(J7-Pad34)") (class "Default")
      (node (ref "J7") (pin "34") (pinfunction "34_34") (pintype "bidirectional"))
    )
    (net (code "202") (name "unconnected-(J7-Pad35)") (class "Default")
      (node (ref "J7") (pin "35") (pinfunction "35_35") (pintype "bidirectional"))
    )
    (net (code "203") (name "unconnected-(J7-Pad36)") (class "Default")
      (node (ref "J7") (pin "36") (pinfunction "36_36") (pintype "bidirectional"))
    )
    (net (code "204") (name "unconnected-(J7-Pad37)") (class "Default")
      (node (ref "J7") (pin "37") (pinfunction "37_37") (pintype "bidirectional"))
    )
    (net (code "205") (name "unconnected-(J7-Pad38)") (class "Default")
      (node (ref "J7") (pin "38") (pinfunction "38_38") (pintype "bidirectional"))
    )
    (net (code "206") (name "unconnected-(J7-Pad39)") (class "Default")
      (node (ref "J7") (pin "39") (pinfunction "39_39") (pintype "bidirectional"))
    )
    (net (code "207") (name "unconnected-(J7-Pad40)") (class "Default")
      (node (ref "J7") (pin "40") (pinfunction "40_40") (pintype "bidirectional"))
    )
    (net (code "208") (name "unconnected-(J7-Pad41)") (class "Default")
      (node (ref "J7") (pin "41") (pinfunction "41_41") (pintype "bidirectional"))
    )
    (net (code "209") (name "unconnected-(J7-Pad42)") (class "Default")
      (node (ref "J7") (pin "42") (pinfunction "42_42") (pintype "bidirectional"))
    )
    (net (code "210") (name "unconnected-(J7-Pad43)") (class "Default")
      (node (ref "J7") (pin "43") (pinfunction "43_43") (pintype "bidirectional"))
    )
    (net (code "211") (name "unconnected-(J7-Pad44)") (class "Default")
      (node (ref "J7") (pin "44") (pinfunction "44_44") (pintype "bidirectional"))
    )
    (net (code "212") (name "unconnected-(J7-Pad45)") (class "Default")
      (node (ref "J7") (pin "45") (pinfunction "45_45") (pintype "bidirectional"))
    )
    (net (code "213") (name "unconnected-(J7-Pad46)") (class "Default")
      (node (ref "J7") (pin "46") (pinfunction "46_46") (pintype "bidirectional"))
    )
    (net (code "214") (name "unconnected-(J7-Pad47)") (class "Default")
      (node (ref "J7") (pin "47") (pinfunction "47_47") (pintype "bidirectional"))
    )
    (net (code "215") (name "unconnected-(J7-Pad48)") (class "Default")
      (node (ref "J7") (pin "48") (pinfunction "48_48") (pintype "bidirectional"))
    )
    (net (code "216") (name "unconnected-(U14C-O-Pad10)") (class "Default")
      (node (ref "U14") (pin "10") (pinfunction "O_10") (pintype "output"))
    )
    (net (code "217") (name "unconnected-(U14D-O-Pad13)") (class "Default")
      (node (ref "U14") (pin "13") (pinfunction "O_13") (pintype "output"))
    )
  )
)
